# cosmicpifpgaOHL.net
KiCad netlist of a schematic drawn in EAGLE
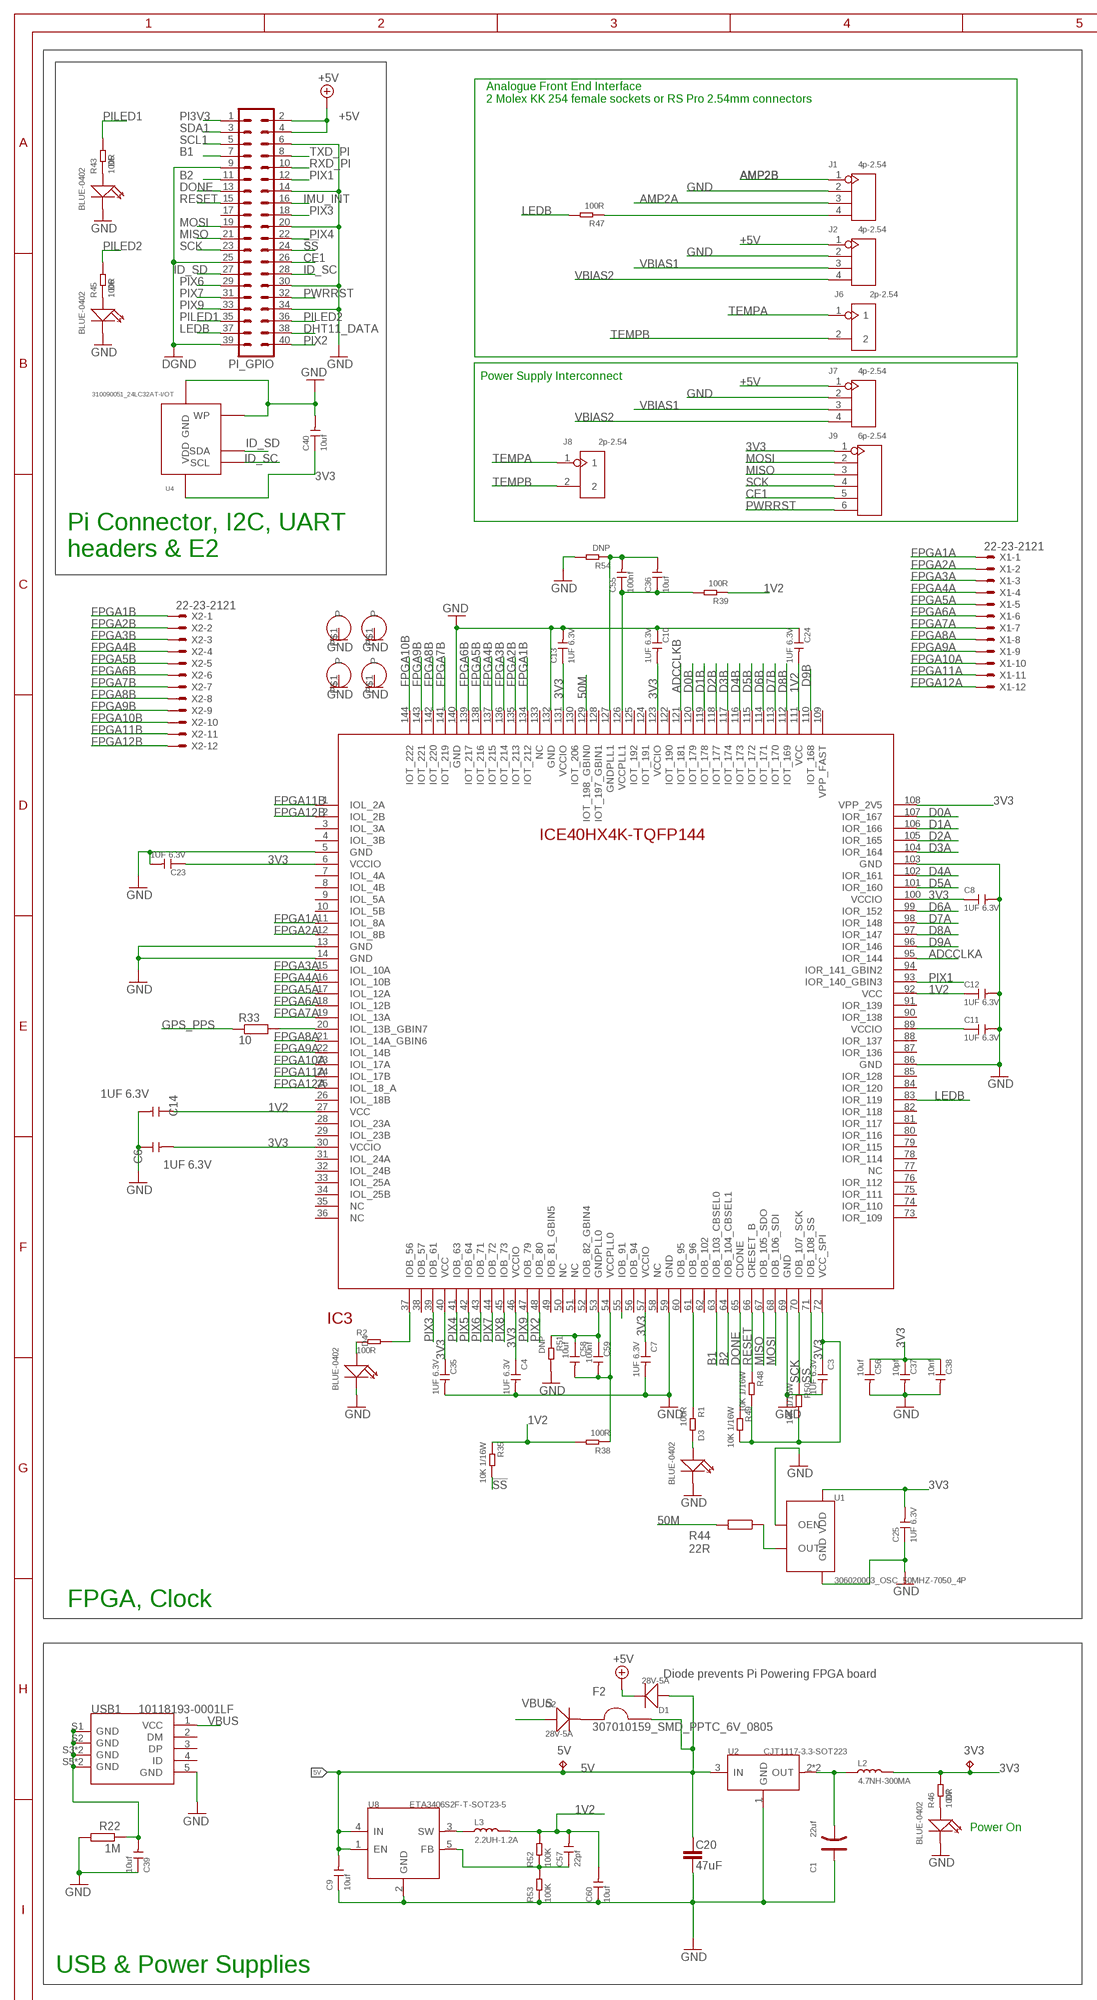
[diagram p0: schematic, sheet 1, part 1 of 2]
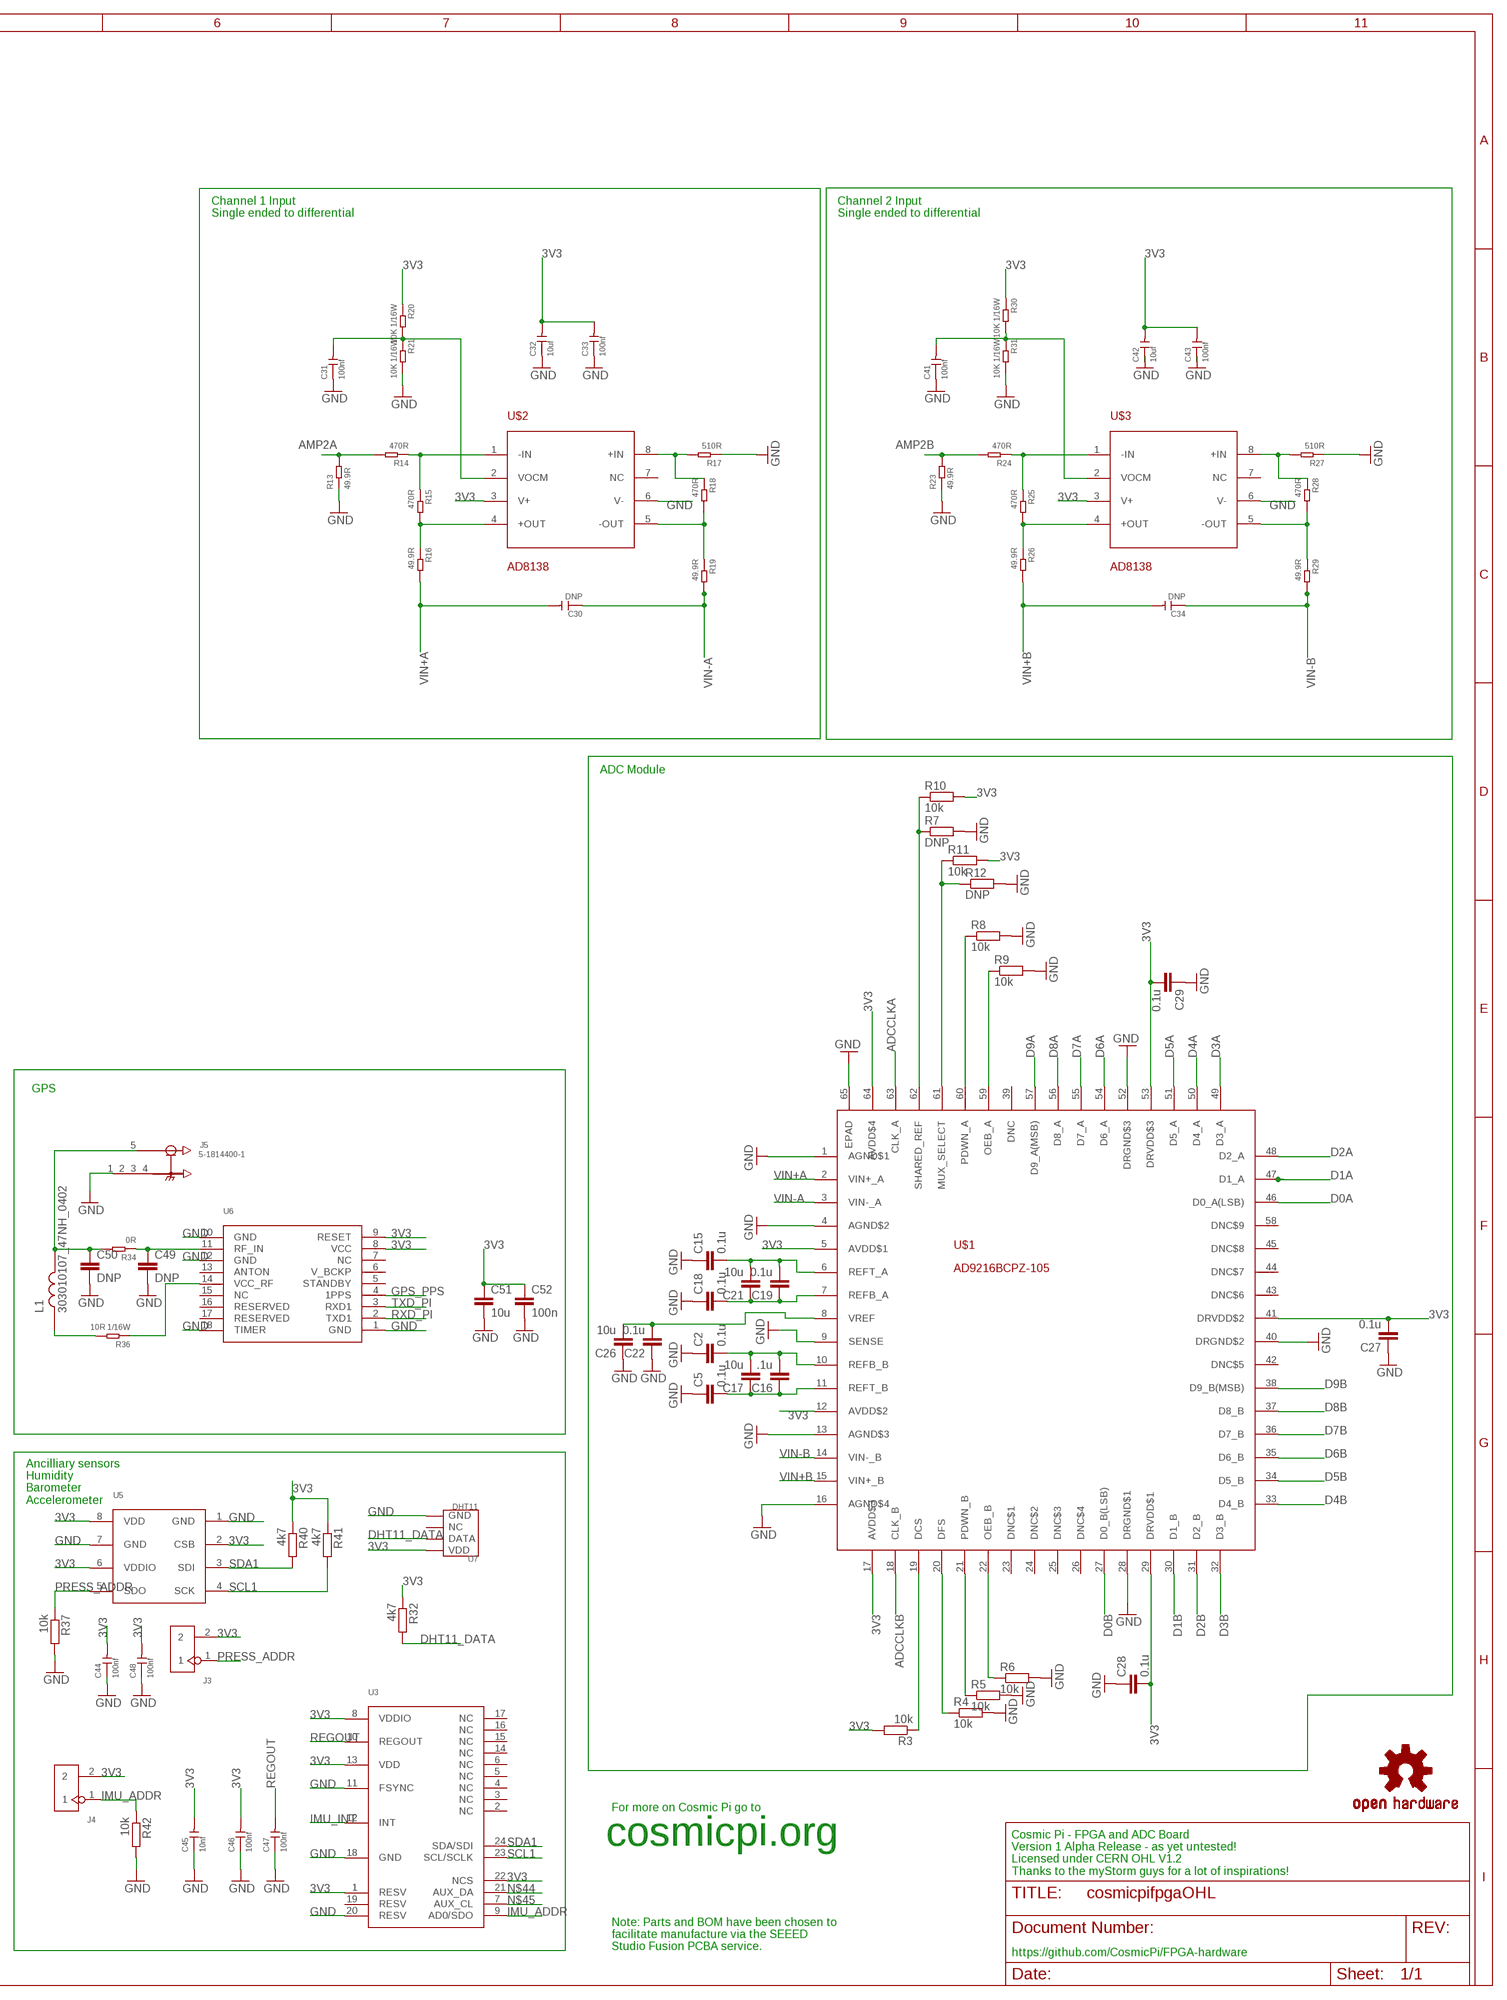
[diagram p1: schematic, sheet 1, part 2 of 2]

(export (version "E")
  (design (tool "Eeschema 10.0.6"))
  (components
    (comp (ref "3V3")
      (value "TPB1,27")
      (footprint "eagle-import:B1,27")
      (libsource (lib "eagle-import") (part "TPB1,27"))
    )
    (comp (ref "5V")
      (value "TPB1,27")
      (footprint "eagle-import:B1,27")
      (libsource (lib "eagle-import") (part "TPB1,27"))
    )
    (comp (ref "C1")
      (value "22uf")
      (footprint "eagle-import:AVX-B")
      (fields (field (name "MPN") "TAJB226K010RNJ"))
      (libsource (lib "eagle-import") (part "TANTALUM-SMD-22UF-10V-10%(AVX-B)"))
    )
    (comp (ref "C2")
      (value "0.1u")
      (footprint "eagle-import:C0402")
      (libsource (lib "eagle-import") (part "C-EUC0402"))
    )
    (comp (ref "C3")
      (value "1UF 6.3V")
      (footprint "eagle-import:C0402")
      (fields (field (name "MPN") "CC0402KRX5R5BB105"))
      (libsource (lib "eagle-import") (part "CERAMIC-1UF-6.3V-10%-X5R(0402)"))
    )
    (comp (ref "C4")
      (value "1UF 6.3V")
      (footprint "eagle-import:C0402")
      (fields (field (name "MPN") "CC0402KRX5R5BB105"))
      (libsource (lib "eagle-import") (part "CERAMIC-1UF-6.3V-10%-X5R(0402)"))
    )
    (comp (ref "C5")
      (value "0.1u")
      (footprint "eagle-import:C0402")
      (libsource (lib "eagle-import") (part "C-EUC0402"))
    )
    (comp (ref "C6")
      (value "1UF 6.3V")
      (footprint "eagle-import:C0402")
      (fields (field (name "MPN") "CC0402KRX5R5BB105"))
      (libsource (lib "eagle-import") (part "CERAMIC-1UF-6.3V-10%-X5R(0402)"))
    )
    (comp (ref "C7")
      (value "1UF 6.3V")
      (footprint "eagle-import:C0402")
      (fields (field (name "MPN") "CC0402KRX5R5BB105"))
      (libsource (lib "eagle-import") (part "CERAMIC-1UF-6.3V-10%-X5R(0402)"))
    )
    (comp (ref "C8")
      (value "1UF 6.3V")
      (footprint "eagle-import:C0402")
      (fields (field (name "MPN") "CC0402KRX5R5BB105"))
      (libsource (lib "eagle-import") (part "CERAMIC-1UF-6.3V-10%-X5R(0402)"))
    )
    (comp (ref "C9")
      (value "10uf")
      (footprint "eagle-import:C0402")
      (fields (field (name "MPN") "CC0402MRX5R5BB106"))
      (libsource (lib "eagle-import") (part "CERAMIC-10UF-6.3V-20%-X5R(0402)"))
    )
    (comp (ref "C10")
      (value "1UF 6.3V")
      (footprint "eagle-import:C0402")
      (fields (field (name "MPN") "CC0402KRX5R5BB105"))
      (libsource (lib "eagle-import") (part "CERAMIC-1UF-6.3V-10%-X5R(0402)"))
    )
    (comp (ref "C11")
      (value "1UF 6.3V")
      (footprint "eagle-import:C0402")
      (fields (field (name "MPN") "CC0402KRX5R5BB105"))
      (libsource (lib "eagle-import") (part "CERAMIC-1UF-6.3V-10%-X5R(0402)"))
    )
    (comp (ref "C12")
      (value "1UF 6.3V")
      (footprint "eagle-import:C0402")
      (fields (field (name "MPN") "CC0402KRX5R5BB105"))
      (libsource (lib "eagle-import") (part "CERAMIC-1UF-6.3V-10%-X5R(0402)"))
    )
    (comp (ref "C13")
      (value "1UF 6.3V")
      (footprint "eagle-import:C0402")
      (fields (field (name "MPN") "CC0402KRX5R5BB105"))
      (libsource (lib "eagle-import") (part "CERAMIC-1UF-6.3V-10%-X5R(0402)"))
    )
    (comp (ref "C14")
      (value "1UF 6.3V")
      (footprint "eagle-import:C0402")
      (fields (field (name "MPN") "CC0402KRX5R5BB105"))
      (libsource (lib "eagle-import") (part "CERAMIC-1UF-6.3V-10%-X5R(0402)"))
    )
    (comp (ref "C15")
      (value "0.1u")
      (footprint "eagle-import:C0402")
      (libsource (lib "eagle-import") (part "C-EUC0402"))
    )
    (comp (ref "C16")
      (value ".1u")
      (footprint "eagle-import:C0402")
      (libsource (lib "eagle-import") (part "C-EUC0402"))
    )
    (comp (ref "C17")
      (value "10u")
      (footprint "eagle-import:C0402")
      (libsource (lib "eagle-import") (part "C-EUC0402"))
    )
    (comp (ref "C18")
      (value "0.1u")
      (footprint "eagle-import:C0402")
      (libsource (lib "eagle-import") (part "C-EUC0402"))
    )
    (comp (ref "C19")
      (value "0.1u")
      (footprint "eagle-import:C0402")
      (libsource (lib "eagle-import") (part "C-EUC0402"))
    )
    (comp (ref "C20")
      (value "47uF")
      (footprint "eagle-import:1206")
      (libsource (lib "eagle-import") (part "C_1206"))
    )
    (comp (ref "C21")
      (value "10u")
      (footprint "eagle-import:C0402")
      (libsource (lib "eagle-import") (part "C-EUC0402"))
    )
    (comp (ref "C22")
      (value "0.1u")
      (footprint "eagle-import:C0402")
      (libsource (lib "eagle-import") (part "C-EUC0402"))
    )
    (comp (ref "C23")
      (value "1UF 6.3V")
      (footprint "eagle-import:C0402")
      (fields (field (name "MPN") "CC0402KRX5R5BB105"))
      (libsource (lib "eagle-import") (part "CERAMIC-1UF-6.3V-10%-X5R(0402)"))
    )
    (comp (ref "C24")
      (value "1UF 6.3V")
      (footprint "eagle-import:C0402")
      (fields (field (name "MPN") "CC0402KRX5R5BB105"))
      (libsource (lib "eagle-import") (part "CERAMIC-1UF-6.3V-10%-X5R(0402)"))
    )
    (comp (ref "C25")
      (value "1UF 6.3V")
      (footprint "eagle-import:C0402")
      (fields (field (name "MPN") "CC0402KRX5R5BB105"))
      (libsource (lib "eagle-import") (part "CERAMIC-1UF-6.3V-10%-X5R(0402)"))
    )
    (comp (ref "C26")
      (value "10u")
      (footprint "eagle-import:C0402")
      (libsource (lib "eagle-import") (part "C-EUC0402"))
    )
    (comp (ref "C27")
      (value "0.1u")
      (footprint "eagle-import:C0402")
      (libsource (lib "eagle-import") (part "C-EUC0402"))
    )
    (comp (ref "C28")
      (value "0.1u")
      (footprint "eagle-import:C0402")
      (libsource (lib "eagle-import") (part "C-EUC0402"))
    )
    (comp (ref "C29")
      (value "0.1u")
      (footprint "eagle-import:C0402")
      (libsource (lib "eagle-import") (part "C-EUC0402"))
    )
    (comp (ref "C30")
      (value "DNP")
      (footprint "eagle-import:C0603")
      (fields (field (name "MPN") "CC0603KRX7R9BB104"))
      (libsource (lib "eagle-import") (part "CERAMIC-100NF-50V-10%-X7R(0603)"))
    )
    (comp (ref "C31")
      (value "100nf")
      (footprint "eagle-import:C0402")
      (fields (field (name "MPN") "CC0402KRX7R8BB104"))
      (libsource (lib "eagle-import") (part "CERAMIC-100NF-25V-10%-X7R(0402)"))
    )
    (comp (ref "C32")
      (value "10uf")
      (footprint "eagle-import:C0402")
      (fields (field (name "MPN") "CC0402MRX5R5BB106"))
      (libsource (lib "eagle-import") (part "CERAMIC-10UF-6.3V-20%-X5R(0402)"))
    )
    (comp (ref "C33")
      (value "100nf")
      (footprint "eagle-import:C0402")
      (fields (field (name "MPN") "CC0402KRX7R8BB104"))
      (libsource (lib "eagle-import") (part "CERAMIC-100NF-25V-10%-X7R(0402)"))
    )
    (comp (ref "C34")
      (value "DNP")
      (footprint "eagle-import:C0603")
      (fields (field (name "MPN") "CC0603KRX7R9BB104"))
      (libsource (lib "eagle-import") (part "CERAMIC-100NF-50V-10%-X7R(0603)"))
    )
    (comp (ref "C35")
      (value "1UF 6.3V")
      (footprint "eagle-import:C0402")
      (fields (field (name "MPN") "CC0402KRX5R5BB105"))
      (libsource (lib "eagle-import") (part "CERAMIC-1UF-6.3V-10%-X5R(0402)"))
    )
    (comp (ref "C36")
      (value "10uf")
      (footprint "eagle-import:C0402")
      (fields (field (name "MPN") "CC0402MRX5R5BB106"))
      (libsource (lib "eagle-import") (part "CERAMIC-10UF-6.3V-20%-X5R(0402)"))
    )
    (comp (ref "C37")
      (value "10pf")
      (footprint "eagle-import:C0402")
      (fields (field (name "MPN") "CC0402JRNPO9BN100"))
      (libsource (lib "eagle-import") (part "CERAMIC-10PF-50V-5%-NPO(0402)"))
    )
    (comp (ref "C38")
      (value "10nf")
      (footprint "eagle-import:C0402")
      (fields (field (name "MPN") "CC0402KRX7R9BB103"))
      (libsource (lib "eagle-import") (part "CERAMIC-10NF-50V-10%-X7R(0402)"))
    )
    (comp (ref "C39")
      (value "10uf")
      (footprint "eagle-import:C0402")
      (fields (field (name "MPN") "CC0402MRX5R5BB106"))
      (libsource (lib "eagle-import") (part "CERAMIC-10UF-6.3V-20%-X5R(0402)"))
    )
    (comp (ref "C40")
      (value "10uf")
      (footprint "eagle-import:C0402")
      (fields (field (name "MPN") "CC0402MRX5R5BB106"))
      (libsource (lib "eagle-import") (part "Seeed-Capacitor_464_CERAMIC-10UF-6.3V-20%-X5R(0402)"))
    )
    (comp (ref "C41")
      (value "100nf")
      (footprint "eagle-import:C0402")
      (fields (field (name "MPN") "CC0402KRX7R8BB104"))
      (libsource (lib "eagle-import") (part "CERAMIC-100NF-25V-10%-X7R(0402)"))
    )
    (comp (ref "C42")
      (value "10uf")
      (footprint "eagle-import:C0402")
      (fields (field (name "MPN") "CC0402MRX5R5BB106"))
      (libsource (lib "eagle-import") (part "CERAMIC-10UF-6.3V-20%-X5R(0402)"))
    )
    (comp (ref "C43")
      (value "100nf")
      (footprint "eagle-import:C0402")
      (fields (field (name "MPN") "CC0402KRX7R8BB104"))
      (libsource (lib "eagle-import") (part "CERAMIC-100NF-25V-10%-X7R(0402)"))
    )
    (comp (ref "C44")
      (value "100nf")
      (footprint "eagle-import:C0402")
      (fields (field (name "MPN") "CC0402KRX7R8BB104"))
      (libsource (lib "eagle-import") (part "Seeed-Capacitor_464_CERAMIC-100NF-25V-10%-X7R(0402)"))
    )
    (comp (ref "C45")
      (value "10nf")
      (footprint "eagle-import:C0402")
      (fields (field (name "MPN") "CC0402KRX7R9BB103"))
      (libsource (lib "eagle-import") (part "Seeed-Capacitor_464_CERAMIC-10NF-50V-10%-X7R(0402)"))
    )
    (comp (ref "C46")
      (value "100nf")
      (footprint "eagle-import:C0402")
      (fields (field (name "MPN") "CC0402KRX7R8BB104"))
      (libsource (lib "eagle-import") (part "Seeed-Capacitor_464_CERAMIC-100NF-25V-10%-X7R(0402)"))
    )
    (comp (ref "C47")
      (value "100nf")
      (footprint "eagle-import:C0402")
      (fields (field (name "MPN") "CC0402KRX7R8BB104"))
      (libsource (lib "eagle-import") (part "Seeed-Capacitor_464_CERAMIC-100NF-25V-10%-X7R(0402)"))
    )
    (comp (ref "C48")
      (value "100nf")
      (footprint "eagle-import:C0402")
      (fields (field (name "MPN") "CC0402KRX7R8BB104"))
      (libsource (lib "eagle-import") (part "Seeed-Capacitor_464_CERAMIC-100NF-25V-10%-X7R(0402)"))
    )
    (comp (ref "C49")
      (value "DNP")
      (footprint "eagle-import:C0402")
      (libsource (lib "eagle-import") (part "C-EUC0402"))
    )
    (comp (ref "C50")
      (value "DNP")
      (footprint "eagle-import:C0402")
      (libsource (lib "eagle-import") (part "C-EUC0402"))
    )
    (comp (ref "C51")
      (value "10u")
      (footprint "eagle-import:C0402")
      (libsource (lib "eagle-import") (part "C-EUC0402"))
    )
    (comp (ref "C52")
      (value "100n")
      (footprint "eagle-import:C0402")
      (libsource (lib "eagle-import") (part "C-EUC0402"))
    )
    (comp (ref "C55")
      (value "100nf")
      (footprint "eagle-import:C0402")
      (fields (field (name "MPN") "CC0402KRX7R8BB104"))
      (libsource (lib "eagle-import") (part "Seeed-Capacitor_464_CERAMIC-100NF-25V-10%-X7R(0402)"))
    )
    (comp (ref "C56")
      (value "10uf")
      (footprint "eagle-import:C0402")
      (fields (field (name "MPN") "CC0402MRX5R5BB106"))
      (libsource (lib "eagle-import") (part "CERAMIC-10UF-6.3V-20%-X5R(0402)"))
    )
    (comp (ref "C57")
      (value "22pf")
      (footprint "eagle-import:C0402")
      (fields (field (name "MPN") "CC0402JRNPO9BN220"))
      (libsource (lib "eagle-import") (part "CERAMIC-22PF-50V-5%-NPO(0402)"))
    )
    (comp (ref "C58")
      (value "10uf")
      (footprint "eagle-import:C0402")
      (fields (field (name "MPN") "CC0402MRX5R5BB106"))
      (libsource (lib "eagle-import") (part "CERAMIC-10UF-6.3V-20%-X5R(0402)"))
    )
    (comp (ref "C59")
      (value "100nf")
      (footprint "eagle-import:C0402")
      (fields (field (name "MPN") "CC0402KRX7R8BB104"))
      (libsource (lib "eagle-import") (part "CERAMIC-100NF-25V-10%-X7R(0402)"))
    )
    (comp (ref "C60")
      (value "10uf")
      (footprint "eagle-import:C0402")
      (fields (field (name "MPN") "CC0402MRX5R5BB106"))
      (libsource (lib "eagle-import") (part "CERAMIC-10UF-6.3V-20%-X5R(0402)"))
    )
    (comp (ref "D1")
      (value "28V-5A")
      (footprint "eagle-import:DO-214AA")
      (fields (field (name "MPN") "SS54B"))
      (libsource (lib "eagle-import") (part "SMD-DIODE-SCHOTTKY-28V-5A(DO-214AA)"))
    )
    (comp (ref "D2")
      (value "28V-5A")
      (footprint "eagle-import:DO-214AA")
      (fields (field (name "MPN") "SS54B"))
      (libsource (lib "eagle-import") (part "SMD-DIODE-SCHOTTKY-28V-5A(DO-214AA)"))
    )
    (comp (ref "D3")
      (value "BLUE-0402")
      (footprint "eagle-import:LED-0402")
      (fields (field (name "MPN") "BL-HB337A-AV-TRB"))
      (libsource (lib "eagle-import") (part "SMD-LED-CLEAR-BLUE(0402)"))
    )
    (comp (ref "D4")
      (value "BLUE-0402")
      (footprint "eagle-import:LED-0402")
      (fields (field (name "MPN") "BL-HB337A-AV-TRB"))
      (libsource (lib "eagle-import") (part "SMD-LED-CLEAR-BLUE(0402)"))
    )
    (comp (ref "D5")
      (value "BLUE-0402")
      (footprint "eagle-import:LED-0402")
      (fields (field (name "MPN") "BL-HB337A-AV-TRB"))
      (libsource (lib "eagle-import") (part "SMD-LED-CLEAR-BLUE(0402)"))
    )
    (comp (ref "D6")
      (value "BLUE-0402")
      (footprint "eagle-import:LED-0402")
      (fields (field (name "MPN") "BL-HB337A-AV-TRB"))
      (libsource (lib "eagle-import") (part "SMD-LED-CLEAR-BLUE(0402)"))
    )
    (comp (ref "D7")
      (value "BLUE-0402")
      (footprint "eagle-import:LED-0402")
      (fields (field (name "MPN") "BL-HB337A-AV-TRB"))
      (libsource (lib "eagle-import") (part "SMD-LED-CLEAR-BLUE(0402)"))
    )
    (comp (ref "F2")
      (value "307010159_SMD_PPTC_6V_0805")
      (footprint "eagle-import:F0805")
      (libsource (lib "eagle-import") (part "307010159_SMD_PPTC_6V_0805"))
    )
    (comp (ref "IC3")
      (value "ICE40HX4K_TQFP144")
      (footprint "eagle-import:TQFP144")
      (libsource (lib "eagle-import") (part "ICE40HX4K_TQFP144"))
    )
    (comp (ref "J1")
      (value "4p-2.54")
      (footprint "eagle-import:H4-2.54")
      (fields (field (name "MPN") "F185-1104A1BSYA1"))
      (libsource (lib "eagle-import") (part "DIP-BLACK-FEMALE-HEADER-VERT(4P-2.54)"))
    )
    (comp (ref "J2")
      (value "4p-2.54")
      (footprint "eagle-import:H4-2.54")
      (fields (field (name "MPN") "F185-1104A1BSYA1"))
      (libsource (lib "eagle-import") (part "DIP-BLACK-FEMALE-HEADER-VERT(4P-2.54)"))
    )
    (comp (ref "J3")
      (value "DIP-BLACK-JUMPER")
      (footprint "eagle-import:H2-2.54")
      (libsource (lib "eagle-import") (part "DIP-BLACK-JUMPER"))
    )
    (comp (ref "J4")
      (value "DIP-BLACK-JUMPER")
      (footprint "eagle-import:H2-2.54")
      (libsource (lib "eagle-import") (part "DIP-BLACK-JUMPER"))
    )
    (comp (ref "J5")
      (value "5-1814400-1")
      (footprint "eagle-import:TE_5-1814400-1")
      (libsource (lib "eagle-import") (part "5-1814400-1"))
    )
    (comp (ref "J6")
      (value "2p-2.54")
      (footprint "eagle-import:H2-2.54")
      (fields (field (name "MPN") "P125-1102A0BS116A1"))
      (libsource (lib "eagle-import") (part "DIP-BLACK-MALE-HEADER-VERT(2P-2.54)"))
    )
    (comp (ref "J7")
      (value "4p-2.54")
      (footprint "eagle-import:H4-2.54")
      (fields (field (name "MPN") "F185-1104A1BSYA1"))
      (libsource (lib "eagle-import") (part "DIP-BLACK-FEMALE-HEADER-VERT(4P-2.54)"))
    )
    (comp (ref "J8")
      (value "2p-2.54")
      (footprint "eagle-import:H2-2.54")
      (fields (field (name "MPN") "P125-1102A0BS116A1"))
      (libsource (lib "eagle-import") (part "DIP-BLACK-MALE-HEADER-VERT(2P-2.54)"))
    )
    (comp (ref "J9")
      (value "6p-2.54")
      (footprint "eagle-import:H6-2.54")
      (fields (field (name "MPN") "F185-1106A1BSYA2"))
      (libsource (lib "eagle-import") (part "DIP-LONG-BLACK-FEMALE-HEADER-VERT(6P-2.54)"))
    )
    (comp (ref "L1")
      (value "303010107_47NH_0402")
      (footprint "eagle-import:L0402")
      (libsource (lib "eagle-import") (part "303010107_47NH_0402"))
    )
    (comp (ref "L2")
      (value "4.7NH-300MA")
      (footprint "eagle-import:L0402")
      (fields (field (name "MPN") "LQG15HS4N7S02"))
      (libsource (lib "eagle-import") (part "SMD-INDUCTOR-4.7NH-0.3NH-300MA(0402)"))
    )
    (comp (ref "L3")
      (value "2.2UH-1.2A")
      (footprint "eagle-import:L0805")
      (fields (field (name "MPN") "LQM2MPN2R2MG0"))
      (libsource (lib "eagle-import") (part "SMD-INDUCTOR-2.2UH-20%-1.2A(0805)"))
    )
    (comp (ref "OSHW")
      (value "OSHW-LOGOL")
      (footprint "eagle-import:OSHW-LOGO-L")
      (libsource (lib "eagle-import") (part "OSHW-LOGOL"))
    )
    (comp (ref "PI_GPIO")
      (value "MA20-2")
      (footprint "eagle-import:MA20-2")
      (libsource (lib "eagle-import") (part "MA20-2"))
    )
    (comp (ref "R1")
      (value "100R")
      (footprint "eagle-import:R0402")
      (fields (field (name "MPN") "RC0402JR-07100RL"))
      (libsource (lib "eagle-import") (part "Seeed-Resistor_474_SMD-RES-100R-5%-1/16W(0402)"))
    )
    (comp (ref "R2")
      (value "100R")
      (footprint "eagle-import:R0402")
      (fields (field (name "MPN") "RC0402JR-07100RL"))
      (libsource (lib "eagle-import") (part "Seeed-Resistor_474_SMD-RES-100R-5%-1/16W(0402)"))
    )
    (comp (ref "R3")
      (value "10k")
      (footprint "eagle-import:R0402")
      (libsource (lib "eagle-import") (part "R-EU_R0402"))
    )
    (comp (ref "R4")
      (value "10k")
      (footprint "eagle-import:R0402")
      (libsource (lib "eagle-import") (part "R-EU_R0402"))
    )
    (comp (ref "R5")
      (value "10k")
      (footprint "eagle-import:R0402")
      (libsource (lib "eagle-import") (part "R-EU_R0402"))
    )
    (comp (ref "R6")
      (value "10k")
      (footprint "eagle-import:R0402")
      (libsource (lib "eagle-import") (part "R-EU_R0402"))
    )
    (comp (ref "R7")
      (value "DNP")
      (footprint "eagle-import:R0402")
      (libsource (lib "eagle-import") (part "R-EU_R0402"))
    )
    (comp (ref "R8")
      (value "10k")
      (footprint "eagle-import:R0402")
      (libsource (lib "eagle-import") (part "R-EU_R0402"))
    )
    (comp (ref "R9")
      (value "10k")
      (footprint "eagle-import:R0402")
      (libsource (lib "eagle-import") (part "R-EU_R0402"))
    )
    (comp (ref "R10")
      (value "10k")
      (footprint "eagle-import:R0402")
      (libsource (lib "eagle-import") (part "R-EU_R0402"))
    )
    (comp (ref "R11")
      (value "10k")
      (footprint "eagle-import:R0402")
      (libsource (lib "eagle-import") (part "R-EU_R0402"))
    )
    (comp (ref "R12")
      (value "DNP")
      (footprint "eagle-import:R0402")
      (libsource (lib "eagle-import") (part "R-EU_R0402"))
    )
    (comp (ref "R13")
      (value "49.9R")
      (footprint "eagle-import:R0603")
      (fields (field (name "MPN") "RC0603FR-0749R9L"))
      (libsource (lib "eagle-import") (part "SMD-RES-49.9R-1%-1/10W(0603)"))
    )
    (comp (ref "R14")
      (value "470R")
      (footprint "eagle-import:R0603")
      (fields (field (name "MPN") "RC0603JR-07470RL"))
      (libsource (lib "eagle-import") (part "SMD-RES-470R-5%-1/10W(0603)"))
    )
    (comp (ref "R15")
      (value "470R")
      (footprint "eagle-import:R0603")
      (fields (field (name "MPN") "RC0603JR-07470RL"))
      (libsource (lib "eagle-import") (part "SMD-RES-470R-5%-1/10W(0603)"))
    )
    (comp (ref "R16")
      (value "49.9R")
      (footprint "eagle-import:R0603")
      (fields (field (name "MPN") "RC0603FR-0749R9L"))
      (libsource (lib "eagle-import") (part "SMD-RES-49.9R-1%-1/10W(0603)"))
    )
    (comp (ref "R17")
      (value "510R")
      (footprint "eagle-import:R0603")
      (fields (field (name "MPN") "RC0603JR-07510RL"))
      (libsource (lib "eagle-import") (part "SMD-RES-510R-5%-1/10W(0603)"))
    )
    (comp (ref "R18")
      (value "470R")
      (footprint "eagle-import:R0603")
      (fields (field (name "MPN") "RC0603JR-07470RL"))
      (libsource (lib "eagle-import") (part "SMD-RES-470R-5%-1/10W(0603)"))
    )
    (comp (ref "R19")
      (value "49.9R")
      (footprint "eagle-import:R0603")
      (fields (field (name "MPN") "RC0603FR-0749R9L"))
      (libsource (lib "eagle-import") (part "SMD-RES-49.9R-1%-1/10W(0603)"))
    )
    (comp (ref "R20")
      (value "10K 1/16W")
      (footprint "eagle-import:R0402")
      (fields (field (name "MPN") "RC0402FR-0710KL"))
      (libsource (lib "eagle-import") (part "SMD-RES-10K-1%-1/16W(0402)"))
    )
    (comp (ref "R21")
      (value "10K 1/16W")
      (footprint "eagle-import:R0402")
      (fields (field (name "MPN") "RC0402FR-0710KL"))
      (libsource (lib "eagle-import") (part "SMD-RES-10K-1%-1/16W(0402)"))
    )
    (comp (ref "R22")
      (value "1M")
      (footprint "eagle-import:R0402")
      (libsource (lib "eagle-import") (part "R-EU_R0402"))
    )
    (comp (ref "R23")
      (value "49.9R")
      (footprint "eagle-import:R0603")
      (fields (field (name "MPN") "RC0603FR-0749R9L"))
      (libsource (lib "eagle-import") (part "SMD-RES-49.9R-1%-1/10W(0603)"))
    )
    (comp (ref "R24")
      (value "470R")
      (footprint "eagle-import:R0603")
      (fields (field (name "MPN") "RC0603JR-07470RL"))
      (libsource (lib "eagle-import") (part "SMD-RES-470R-5%-1/10W(0603)"))
    )
    (comp (ref "R25")
      (value "470R")
      (footprint "eagle-import:R0603")
      (fields (field (name "MPN") "RC0603JR-07470RL"))
      (libsource (lib "eagle-import") (part "SMD-RES-470R-5%-1/10W(0603)"))
    )
    (comp (ref "R26")
      (value "49.9R")
      (footprint "eagle-import:R0603")
      (fields (field (name "MPN") "RC0603FR-0749R9L"))
      (libsource (lib "eagle-import") (part "SMD-RES-49.9R-1%-1/10W(0603)"))
    )
    (comp (ref "R27")
      (value "510R")
      (footprint "eagle-import:R0603")
      (fields (field (name "MPN") "RC0603JR-07510RL"))
      (libsource (lib "eagle-import") (part "SMD-RES-510R-5%-1/10W(0603)"))
    )
    (comp (ref "R28")
      (value "470R")
      (footprint "eagle-import:R0603")
      (fields (field (name "MPN") "RC0603JR-07470RL"))
      (libsource (lib "eagle-import") (part "SMD-RES-470R-5%-1/10W(0603)"))
    )
    (comp (ref "R29")
      (value "49.9R")
      (footprint "eagle-import:R0603")
      (fields (field (name "MPN") "RC0603FR-0749R9L"))
      (libsource (lib "eagle-import") (part "SMD-RES-49.9R-1%-1/10W(0603)"))
    )
    (comp (ref "R30")
      (value "10K 1/16W")
      (footprint "eagle-import:R0402")
      (fields (field (name "MPN") "RC0402FR-0710KL"))
      (libsource (lib "eagle-import") (part "SMD-RES-10K-1%-1/16W(0402)"))
    )
    (comp (ref "R31")
      (value "10K 1/16W")
      (footprint "eagle-import:R0402")
      (fields (field (name "MPN") "RC0402FR-0710KL"))
      (libsource (lib "eagle-import") (part "SMD-RES-10K-1%-1/16W(0402)"))
    )
    (comp (ref "R32")
      (value "4k7")
      (footprint "eagle-import:R0402")
      (libsource (lib "eagle-import") (part "R-EU_R0402"))
    )
    (comp (ref "R33")
      (value "10")
      (footprint "eagle-import:R0402")
      (libsource (lib "eagle-import") (part "R-EU_R0402"))
    )
    (comp (ref "R34")
      (value "0R")
      (footprint "eagle-import:R0402")
      (fields (field (name "MPN") "RC0402JR-070RL"))
      (libsource (lib "eagle-import") (part "SMD-RES-0R-5%-1/16W(0402)"))
    )
    (comp (ref "R35")
      (value "10K 1/16W")
      (footprint "eagle-import:R0402")
      (fields (field (name "MPN") "RC0402FR-0710KL"))
      (libsource (lib "eagle-import") (part "SMD-RES-10K-1%-1/16W(0402)"))
    )
    (comp (ref "R36")
      (value "10R 1/16W")
      (footprint "eagle-import:R0402")
      (fields (field (name "MPN") "RC0402FR-0710RL"))
      (libsource (lib "eagle-import") (part "SMD-RES-10R-1%-1/16W(0402)"))
    )
    (comp (ref "R37")
      (value "10k")
      (footprint "eagle-import:R0402")
      (libsource (lib "eagle-import") (part "R-EU_R0402"))
    )
    (comp (ref "R38")
      (value "100R")
      (footprint "eagle-import:R0402")
      (fields (field (name "MPN") "RC0402JR-07100RL"))
      (libsource (lib "eagle-import") (part "SMD-RES-100R-5%-1/16W(0402)"))
    )
    (comp (ref "R39")
      (value "100R")
      (footprint "eagle-import:R0402")
      (fields (field (name "MPN") "RC0402JR-07100RL"))
      (libsource (lib "eagle-import") (part "SMD-RES-100R-5%-1/16W(0402)"))
    )
    (comp (ref "R40")
      (value "4k7")
      (footprint "eagle-import:R0402")
      (libsource (lib "eagle-import") (part "R-EU_R0402"))
    )
    (comp (ref "R41")
      (value "4k7")
      (footprint "eagle-import:R0402")
      (libsource (lib "eagle-import") (part "R-EU_R0402"))
    )
    (comp (ref "R42")
      (value "10k")
      (footprint "eagle-import:R0402")
      (libsource (lib "eagle-import") (part "R-EU_R0402"))
    )
    (comp (ref "R43")
      (value "100R")
      (footprint "eagle-import:R0402")
      (fields (field (name "MPN") "RC0402JR-07100RL"))
      (libsource (lib "eagle-import") (part "Seeed-Resistor_474_SMD-RES-100R-5%-1/16W(0402)"))
    )
    (comp (ref "R44")
      (value "22R")
      (footprint "eagle-import:R0402")
      (libsource (lib "eagle-import") (part "R-EU_R0402"))
    )
    (comp (ref "R45")
      (value "100R")
      (footprint "eagle-import:R0402")
      (fields (field (name "MPN") "RC0402JR-07100RL"))
      (libsource (lib "eagle-import") (part "Seeed-Resistor_474_SMD-RES-100R-5%-1/16W(0402)"))
    )
    (comp (ref "R46")
      (value "100R")
      (footprint "eagle-import:R0402")
      (fields (field (name "MPN") "RC0402JR-07100RL"))
      (libsource (lib "eagle-import") (part "Seeed-Resistor_474_SMD-RES-100R-5%-1/16W(0402)"))
    )
    (comp (ref "R47")
      (value "100R")
      (footprint "eagle-import:R0402")
      (fields (field (name "MPN") "RC0402JR-07100RL"))
      (libsource (lib "eagle-import") (part "Seeed-Resistor_474_SMD-RES-100R-5%-1/16W(0402)"))
    )
    (comp (ref "R48")
      (value "10K 1/16W")
      (footprint "eagle-import:R0402")
      (fields (field (name "MPN") "RC0402FR-0710KL"))
      (libsource (lib "eagle-import") (part "SMD-RES-10K-1%-1/16W(0402)"))
    )
    (comp (ref "R49")
      (value "10K 1/16W")
      (footprint "eagle-import:R0402")
      (fields (field (name "MPN") "RC0402FR-0710KL"))
      (libsource (lib "eagle-import") (part "SMD-RES-10K-1%-1/16W(0402)"))
    )
    (comp (ref "R50")
      (value "10K 1/16W")
      (footprint "eagle-import:R0402")
      (fields (field (name "MPN") "RC0402FR-0710KL"))
      (libsource (lib "eagle-import") (part "SMD-RES-10K-1%-1/16W(0402)"))
    )
    (comp (ref "R51")
      (value "DNP")
      (footprint "eagle-import:R0402")
      (fields (field (name "MPN") "RC0402JR-07100RL"))
      (libsource (lib "eagle-import") (part "Seeed-Resistor_474_SMD-RES-100R-5%-1/16W(0402)"))
    )
    (comp (ref "R52")
      (value "100K")
      (footprint "eagle-import:R0402")
      (fields (field (name "MPN") "RC0402FR-07100KL"))
      (libsource (lib "eagle-import") (part "SMD-RES-100K-1%-1/16W(0402)"))
    )
    (comp (ref "R53")
      (value "100K")
      (footprint "eagle-import:R0402")
      (fields (field (name "MPN") "RC0402FR-07100KL"))
      (libsource (lib "eagle-import") (part "SMD-RES-100K-1%-1/16W(0402)"))
    )
    (comp (ref "R54")
      (value "DNP")
      (footprint "eagle-import:R0402")
      (fields (field (name "MPN") "RC0402JR-07100RL"))
      (libsource (lib "eagle-import") (part "SMD-RES-100R-5%-1/16W(0402)"))
    )
    (comp (ref "U$1")
      (value "AD9216BCPZ-105")
      (footprint "eagle-import:QFN50P900X900X100-65N")
      (libsource (lib "eagle-import") (part "AD9216BCPZ-105"))
    )
    (comp (ref "U$2")
      (value "AD8138")
      (footprint "eagle-import:SOP65P490X110-8N")
      (libsource (lib "eagle-import") (part "AD8138"))
    )
    (comp (ref "U$3")
      (value "AD8138")
      (footprint "eagle-import:SOP65P490X110-8N")
      (libsource (lib "eagle-import") (part "AD8138"))
    )
    (comp (ref "U$16")
      (value "HOLE-2.5MM")
      (footprint "eagle-import:2.5MM-HOLE")
      (libsource (lib "eagle-import") (part "HOLE-2.5MM"))
    )
    (comp (ref "U$21")
      (value "HOLE-2.5MM")
      (footprint "eagle-import:2.5MM-HOLE")
      (libsource (lib "eagle-import") (part "HOLE-2.5MM"))
    )
    (comp (ref "U$22")
      (value "HOLE-2.5MM")
      (footprint "eagle-import:2.5MM-HOLE")
      (libsource (lib "eagle-import") (part "HOLE-2.5MM"))
    )
    (comp (ref "U$24")
      (value "HOLE-2.5MM")
      (footprint "eagle-import:2.5MM-HOLE")
      (libsource (lib "eagle-import") (part "HOLE-2.5MM"))
    )
    (comp (ref "U1")
      (value "306020003_OSC_50MHZ-7050_4P")
      (footprint "eagle-import:X7050_4P")
      (libsource (lib "eagle-import") (part "306020003_OSC_50MHZ-7050_4P"))
    )
    (comp (ref "U2")
      (value "CJT1117-3.3-SOT223")
      (footprint "eagle-import:SOT-223")
      (fields (field (name "MPN") "CJT1117-3.3"))
      (libsource (lib "eagle-import") (part "PMIC-CJT1117-3.3(SOT223)"))
    )
    (comp (ref "U3")
      (value "MPU-9250")
      (footprint "eagle-import:MPU-9250")
      (libsource (lib "eagle-import") (part "MPU-9250"))
    )
    (comp (ref "U4")
      (value "310090051_24LC32AT-I/OT")
      (footprint "eagle-import:SOT235")
      (libsource (lib "eagle-import") (part "310090051_24LC32AT-I/OT"))
    )
    (comp (ref "U5")
      (value "BMP280")
      (footprint "eagle-import:BMP280")
      (libsource (lib "eagle-import") (part "BMP280"))
    )
    (comp (ref "U6")
      (value "L70-M39")
      (footprint "eagle-import:L70-M39")
      (libsource (lib "eagle-import") (part "L70-M39"))
    )
    (comp (ref "U7")
      (value "DHT11")
      (footprint "eagle-import:SNR4-2.54-15.5X12.0X5.5MM")
      (libsource (lib "eagle-import") (part "TEM-HUM-DHT11(4P-15.5X12.0MM)"))
    )
    (comp (ref "U8")
      (value "ETA3406S2F-T-SOT23-5")
      (footprint "eagle-import:SOT-23-5")
      (fields (field (name "MPN") "ETA3406S2F-T"))
      (libsource (lib "eagle-import") (part "PMIC-DC-DC-ETA3406S2F-T(SOT23-5)"))
    )
    (comp (ref "USB1")
      (value "10118193-0001LF")
      (footprint "eagle-import:MICRO-USB5+6P-SMD-0.65-B")
      (libsource (lib "eagle-import") (part "MICRO-USB-SMD-B-(10118193-0001LF)"))
    )
    (comp (ref "X1")
      (value "22-23-2121")
      (footprint "eagle-import:22-23-2121")
      (fields (field (name "MF") "MOLEX"))
      (libsource (lib "eagle-import") (part "22-23-2121"))
    )
    (comp (ref "X2")
      (value "22-23-2121")
      (footprint "eagle-import:22-23-2121")
      (fields (field (name "MF") "MOLEX"))
      (libsource (lib "eagle-import") (part "22-23-2121"))
    )
  )
  (nets
    (net (code "1") (name "+5V") (class "Default")
      (node (ref "D1") (pin "-") (pinfunction "-_-") (pintype "passive"))
      (node (ref "J2") (pin "1") (pinfunction "P$1_1") (pintype "bidirectional"))
      (node (ref "J7") (pin "1") (pinfunction "P$1_1") (pintype "bidirectional"))
      (node (ref "PI_GPIO") (pin "2") (pinfunction "2_2") (pintype "passive"))
      (node (ref "PI_GPIO") (pin "4") (pinfunction "4_4") (pintype "passive"))
    )
    (net (code "2") (name "/1V2") (class "Default")
      (node (ref "C12") (pin "1") (pinfunction "1_1") (pintype "passive"))
      (node (ref "C14") (pin "1") (pinfunction "1_1") (pintype "passive"))
      (node (ref "C24") (pin "2") (pinfunction "2_2") (pintype "passive"))
      (node (ref "C57") (pin "2") (pinfunction "2_2") (pintype "passive"))
      (node (ref "C60") (pin "2") (pinfunction "2_2") (pintype "passive"))
      (node (ref "IC3") (pin "111") (pinfunction "VCC_111") (pintype "bidirectional"))
      (node (ref "IC3") (pin "27") (pinfunction "VCC_27") (pintype "bidirectional"))
      (node (ref "IC3") (pin "92") (pinfunction "VCC_92") (pintype "bidirectional"))
      (node (ref "L3") (pin "2") (pinfunction "2_2") (pintype "passive"))
      (node (ref "R35") (pin "1") (pinfunction "1_1") (pintype "passive"))
      (node (ref "R38") (pin "2") (pinfunction "2_2") (pintype "passive"))
      (node (ref "R39") (pin "1") (pinfunction "1_1") (pintype "passive"))
      (node (ref "R52") (pin "2") (pinfunction "2_2") (pintype "passive"))
    )
    (net (code "3") (name "/3V3") (class "Default")
      (node (ref "3V3") (pin "TP") (pinfunction "TP_TP") (pintype "input"))
      (node (ref "C10") (pin "2") (pinfunction "2_2") (pintype "passive"))
      (node (ref "C13") (pin "1") (pinfunction "1_1") (pintype "passive"))
      (node (ref "C23") (pin "1") (pinfunction "1_1") (pintype "passive"))
      (node (ref "C25") (pin "2") (pinfunction "2_2") (pintype "passive"))
      (node (ref "C27") (pin "2") (pinfunction "2_2") (pintype "passive"))
      (node (ref "C28") (pin "2") (pinfunction "2_2") (pintype "passive"))
      (node (ref "C29") (pin "2") (pinfunction "2_2") (pintype "passive"))
      (node (ref "C3") (pin "1") (pinfunction "1_1") (pintype "passive"))
      (node (ref "C32") (pin "2") (pinfunction "2_2") (pintype "passive"))
      (node (ref "C33") (pin "2") (pinfunction "2_2") (pintype "passive"))
      (node (ref "C35") (pin "1") (pinfunction "1_1") (pintype "passive"))
      (node (ref "C37") (pin "1") (pinfunction "1_1") (pintype "passive"))
      (node (ref "C38") (pin "1") (pinfunction "1_1") (pintype "passive"))
      (node (ref "C4") (pin "1") (pinfunction "1_1") (pintype "passive"))
      (node (ref "C40") (pin "1") (pinfunction "1_1") (pintype "passive"))
      (node (ref "C42") (pin "2") (pinfunction "2_2") (pintype "passive"))
      (node (ref "C43") (pin "2") (pinfunction "2_2") (pintype "passive"))
      (node (ref "C44") (pin "2") (pinfunction "2_2") (pintype "passive"))
      (node (ref "C45") (pin "2") (pinfunction "2_2") (pintype "passive"))
      (node (ref "C46") (pin "2") (pinfunction "2_2") (pintype "passive"))
      (node (ref "C48") (pin "2") (pinfunction "2_2") (pintype "passive"))
      (node (ref "C51") (pin "1") (pinfunction "1_1") (pintype "passive"))
      (node (ref "C52") (pin "1") (pinfunction "1_1") (pintype "passive"))
      (node (ref "C56") (pin "1") (pinfunction "1_1") (pintype "passive"))
      (node (ref "C6") (pin "2") (pinfunction "2_2") (pintype "passive"))
      (node (ref "C7") (pin "1") (pinfunction "1_1") (pintype "passive"))
      (node (ref "C8") (pin "1") (pinfunction "1_1") (pintype "passive"))
      (node (ref "IC3") (pin "100") (pinfunction "VCCIO_100") (pintype "bidirectional"))
      (node (ref "IC3") (pin "108") (pinfunction "VPP_2V5_108") (pintype "bidirectional"))
      (node (ref "IC3") (pin "123") (pinfunction "VCCIO_123") (pintype "bidirectional"))
      (node (ref "IC3") (pin "131") (pinfunction "VCCIO_131") (pintype "bidirectional"))
      (node (ref "IC3") (pin "30") (pinfunction "VCCIO_30") (pintype "bidirectional"))
      (node (ref "IC3") (pin "40") (pinfunction "VCC_40") (pintype "bidirectional"))
      (node (ref "IC3") (pin "46") (pinfunction "VCCIO_46") (pintype "bidirectional"))
      (node (ref "IC3") (pin "57") (pinfunction "VCCIO_57") (pintype "bidirectional"))
      (node (ref "IC3") (pin "6") (pinfunction "VCCIO_6") (pintype "bidirectional"))
      (node (ref "IC3") (pin "72") (pinfunction "VCC_SPI_72") (pintype "bidirectional"))
      (node (ref "J3") (pin "2") (pinfunction "2_2") (pintype "bidirectional"))
      (node (ref "J4") (pin "2") (pinfunction "2_2") (pintype "bidirectional"))
      (node (ref "J9") (pin "1") (pinfunction "1_1") (pintype "bidirectional"))
      (node (ref "L2") (pin "2") (pinfunction "2_2") (pintype "passive"))
      (node (ref "R10") (pin "2") (pinfunction "2_2") (pintype "passive"))
      (node (ref "R11") (pin "2") (pinfunction "2_2") (pintype "passive"))
      (node (ref "R20") (pin "1") (pinfunction "1_1") (pintype "passive"))
      (node (ref "R3") (pin "2") (pinfunction "2_2") (pintype "passive"))
      (node (ref "R30") (pin "1") (pinfunction "1_1") (pintype "passive"))
      (node (ref "R32") (pin "1") (pinfunction "1_1") (pintype "passive"))
      (node (ref "R40") (pin "1") (pinfunction "1_1") (pintype "passive"))
      (node (ref "R41") (pin "1") (pinfunction "1_1") (pintype "passive"))
      (node (ref "R46") (pin "2") (pinfunction "2_2") (pintype "passive"))
      (node (ref "R48") (pin "2") (pinfunction "2_2") (pintype "passive"))
      (node (ref "R49") (pin "2") (pinfunction "2_2") (pintype "passive"))
      (node (ref "R50") (pin "2") (pinfunction "2_2") (pintype "passive"))
      (node (ref "U$1") (pin "12") (pinfunction "AVDD$2_12") (pintype "bidirectional"))
      (node (ref "U$1") (pin "17") (pinfunction "AVDD$3_17") (pintype "bidirectional"))
      (node (ref "U$1") (pin "29") (pinfunction "DRVDD$1_29") (pintype "bidirectional"))
      (node (ref "U$1") (pin "41") (pinfunction "DRVDD$2_41") (pintype "bidirectional"))
      (node (ref "U$1") (pin "5") (pinfunction "AVDD$1_5") (pintype "bidirectional"))
      (node (ref "U$1") (pin "53") (pinfunction "DRVDD$3_53") (pintype "bidirectional"))
      (node (ref "U$1") (pin "64") (pinfunction "AVDD$4_64") (pintype "bidirectional"))
      (node (ref "U$2") (pin "3") (pinfunction "V+_3") (pintype "bidirectional"))
      (node (ref "U$3") (pin "3") (pinfunction "V+_3") (pintype "bidirectional"))
      (node (ref "U1") (pin "P$4") (pinfunction "VDD_P$4") (pintype "power_in"))
      (node (ref "U3") (pin "1") (pinfunction "RESV_1") (pintype "bidirectional"))
      (node (ref "U3") (pin "13") (pinfunction "VDD_13") (pintype "bidirectional"))
      (node (ref "U3") (pin "22") (pinfunction "NCS_22") (pintype "bidirectional"))
      (node (ref "U3") (pin "8") (pinfunction "VDDIO_8") (pintype "bidirectional"))
      (node (ref "U4") (pin "4") (pinfunction "VDD_4") (pintype "power_in"))
      (node (ref "U5") (pin "2") (pinfunction "CSB_2") (pintype "bidirectional"))
      (node (ref "U5") (pin "6") (pinfunction "VDDIO_6") (pintype "bidirectional"))
      (node (ref "U5") (pin "8") (pinfunction "VDD_8") (pintype "bidirectional"))
      (node (ref "U6") (pin "8") (pinfunction "VCC_8") (pintype "bidirectional"))
      (node (ref "U6") (pin "9") (pinfunction "RESET_9") (pintype "bidirectional"))
      (node (ref "U7") (pin "1") (pinfunction "VDD_1") (pintype "power_in"))
    )
    (net (code "4") (name "/50M") (class "Default")
      (node (ref "IC3") (pin "129") (pinfunction "IOT_198_GBIN0_129") (pintype "bidirectional"))
      (node (ref "R44") (pin "2") (pinfunction "2_2") (pintype "passive"))
    )
    (net (code "5") (name "/ADCCLKA") (class "Default")
      (node (ref "IC3") (pin "95") (pinfunction "IOR_144_95") (pintype "bidirectional"))
      (node (ref "U$1") (pin "63") (pinfunction "CLK_A_63") (pintype "bidirectional"))
    )
    (net (code "6") (name "/ADCCLKB") (class "Default")
      (node (ref "IC3") (pin "121") (pinfunction "IOT_181_121") (pintype "bidirectional"))
      (node (ref "U$1") (pin "18") (pinfunction "CLK_B_18") (pintype "bidirectional"))
    )
    (net (code "7") (name "/AMP2A") (class "Default")
      (node (ref "J1") (pin "3") (pinfunction "P$3_3") (pintype "bidirectional"))
      (node (ref "R13") (pin "2") (pinfunction "2_2") (pintype "passive"))
      (node (ref "R14") (pin "2") (pinfunction "2_2") (pintype "passive"))
    )
    (net (code "8") (name "/AMP2B") (class "Default")
      (node (ref "J1") (pin "1") (pinfunction "P$1_1") (pintype "bidirectional"))
      (node (ref "R23") (pin "2") (pinfunction "2_2") (pintype "passive"))
      (node (ref "R24") (pin "2") (pinfunction "2_2") (pintype "passive"))
    )
    (net (code "9") (name "/B1") (class "Default")
      (node (ref "IC3") (pin "63") (pinfunction "IOB_103_CBSEL0_63") (pintype "bidirectional"))
      (node (ref "PI_GPIO") (pin "7") (pinfunction "7_7") (pintype "passive"))
    )
    (net (code "10") (name "/B2") (class "Default")
      (node (ref "IC3") (pin "64") (pinfunction "IOB_104_CBSEL1_64") (pintype "bidirectional"))
      (node (ref "PI_GPIO") (pin "11") (pinfunction "11_11") (pintype "passive"))
    )
    (net (code "11") (name "/CE1") (class "Default")
      (node (ref "J9") (pin "5") (pinfunction "5_5") (pintype "bidirectional"))
      (node (ref "PI_GPIO") (pin "26") (pinfunction "26_26") (pintype "passive"))
    )
    (net (code "12") (name "/D0A") (class "Default")
      (node (ref "IC3") (pin "107") (pinfunction "IOR_167_107") (pintype "bidirectional"))
      (node (ref "U$1") (pin "46") (pinfunction "D0_A(LSB)_46") (pintype "bidirectional"))
    )
    (net (code "13") (name "/D0B") (class "Default")
      (node (ref "IC3") (pin "120") (pinfunction "IOT_179_120") (pintype "bidirectional"))
      (node (ref "U$1") (pin "27") (pinfunction "D0_B(LSB)_27") (pintype "bidirectional"))
    )
    (net (code "14") (name "/D1A") (class "Default")
      (node (ref "IC3") (pin "106") (pinfunction "IOR_166_106") (pintype "bidirectional"))
      (node (ref "U$1") (pin "47") (pinfunction "D1_A_47") (pintype "bidirectional"))
    )
    (net (code "15") (name "/D1B") (class "Default")
      (node (ref "IC3") (pin "119") (pinfunction "IOT_178_119") (pintype "bidirectional"))
      (node (ref "U$1") (pin "30") (pinfunction "D1_B_30") (pintype "bidirectional"))
    )
    (net (code "16") (name "/D2A") (class "Default")
      (node (ref "IC3") (pin "105") (pinfunction "IOR_165_105") (pintype "bidirectional"))
      (node (ref "U$1") (pin "48") (pinfunction "D2_A_48") (pintype "bidirectional"))
    )
    (net (code "17") (name "/D2B") (class "Default")
      (node (ref "IC3") (pin "118") (pinfunction "IOT_177_118") (pintype "bidirectional"))
      (node (ref "U$1") (pin "31") (pinfunction "D2_B_31") (pintype "bidirectional"))
    )
    (net (code "18") (name "/D3A") (class "Default")
      (node (ref "IC3") (pin "104") (pinfunction "IOR_164_104") (pintype "bidirectional"))
      (node (ref "U$1") (pin "49") (pinfunction "D3_A_49") (pintype "bidirectional"))
    )
    (net (code "19") (name "/D3B") (class "Default")
      (node (ref "IC3") (pin "117") (pinfunction "IOT_174_117") (pintype "bidirectional"))
      (node (ref "U$1") (pin "32") (pinfunction "D3_B_32") (pintype "bidirectional"))
    )
    (net (code "20") (name "/D4A") (class "Default")
      (node (ref "IC3") (pin "102") (pinfunction "IOR_161_102") (pintype "bidirectional"))
      (node (ref "U$1") (pin "50") (pinfunction "D4_A_50") (pintype "bidirectional"))
    )
    (net (code "21") (name "/D4B") (class "Default")
      (node (ref "IC3") (pin "116") (pinfunction "IOT_173_116") (pintype "bidirectional"))
      (node (ref "U$1") (pin "33") (pinfunction "D4_B_33") (pintype "bidirectional"))
    )
    (net (code "22") (name "/D5A") (class "Default")
      (node (ref "IC3") (pin "101") (pinfunction "IOR_160_101") (pintype "bidirectional"))
      (node (ref "U$1") (pin "51") (pinfunction "D5_A_51") (pintype "bidirectional"))
    )
    (net (code "23") (name "/D5B") (class "Default")
      (node (ref "IC3") (pin "115") (pinfunction "IOT_172_115") (pintype "bidirectional"))
      (node (ref "U$1") (pin "34") (pinfunction "D5_B_34") (pintype "bidirectional"))
    )
    (net (code "24") (name "/D6A") (class "Default")
      (node (ref "IC3") (pin "99") (pinfunction "IOR_152_99") (pintype "bidirectional"))
      (node (ref "U$1") (pin "54") (pinfunction "D6_A_54") (pintype "bidirectional"))
    )
    (net (code "25") (name "/D6B") (class "Default")
      (node (ref "IC3") (pin "114") (pinfunction "IOT_171_114") (pintype "bidirectional"))
      (node (ref "U$1") (pin "35") (pinfunction "D6_B_35") (pintype "bidirectional"))
    )
    (net (code "26") (name "/D7A") (class "Default")
      (node (ref "IC3") (pin "98") (pinfunction "IOR_148_98") (pintype "bidirectional"))
      (node (ref "U$1") (pin "55") (pinfunction "D7_A_55") (pintype "bidirectional"))
    )
    (net (code "27") (name "/D7B") (class "Default")
      (node (ref "IC3") (pin "113") (pinfunction "IOT_170_113") (pintype "bidirectional"))
      (node (ref "U$1") (pin "36") (pinfunction "D7_B_36") (pintype "bidirectional"))
    )
    (net (code "28") (name "/D8A") (class "Default")
      (node (ref "IC3") (pin "97") (pinfunction "IOR_147_97") (pintype "bidirectional"))
      (node (ref "U$1") (pin "56") (pinfunction "D8_A_56") (pintype "bidirectional"))
    )
    (net (code "29") (name "/D8B") (class "Default")
      (node (ref "IC3") (pin "112") (pinfunction "IOT_169_112") (pintype "bidirectional"))
      (node (ref "U$1") (pin "37") (pinfunction "D8_B_37") (pintype "bidirectional"))
    )
    (net (code "30") (name "/D9A") (class "Default")
      (node (ref "IC3") (pin "96") (pinfunction "IOR_146_96") (pintype "bidirectional"))
      (node (ref "U$1") (pin "57") (pinfunction "D9_A(MSB)_57") (pintype "bidirectional"))
    )
    (net (code "31") (name "/D9B") (class "Default")
      (node (ref "IC3") (pin "110") (pinfunction "IOT_168_110") (pintype "bidirectional"))
      (node (ref "U$1") (pin "38") (pinfunction "D9_B(MSB)_38") (pintype "bidirectional"))
    )
    (net (code "32") (name "/DHT11_DATA") (class "Default")
      (node (ref "PI_GPIO") (pin "38") (pinfunction "38_38") (pintype "passive"))
      (node (ref "R32") (pin "2") (pinfunction "2_2") (pintype "passive"))
      (node (ref "U7") (pin "2") (pinfunction "DATA_2") (pintype "bidirectional"))
    )
    (net (code "33") (name "/DONE") (class "Default")
      (node (ref "IC3") (pin "65") (pinfunction "CDONE_65") (pintype "bidirectional"))
      (node (ref "PI_GPIO") (pin "13") (pinfunction "13_13") (pintype "passive"))
      (node (ref "R49") (pin "1") (pinfunction "1_1") (pintype "passive"))
    )
    (net (code "34") (name "/FPGA1A") (class "Default")
      (node (ref "IC3") (pin "11") (pinfunction "IOL_8A_11") (pintype "bidirectional"))
      (node (ref "X1") (pin "1") (pinfunction "S_1") (pintype "passive"))
    )
    (net (code "35") (name "/FPGA1B") (class "Default")
      (node (ref "IC3") (pin "134") (pinfunction "IOT_212_134") (pintype "bidirectional"))
      (node (ref "X2") (pin "1") (pinfunction "S_1") (pintype "passive"))
    )
    (net (code "36") (name "/FPGA2A") (class "Default")
      (node (ref "IC3") (pin "12") (pinfunction "IOL_8B_12") (pintype "bidirectional"))
      (node (ref "X1") (pin "2") (pinfunction "S_2") (pintype "passive"))
    )
    (net (code "37") (name "/FPGA2B") (class "Default")
      (node (ref "IC3") (pin "135") (pinfunction "IOT_213_135") (pintype "bidirectional"))
      (node (ref "X2") (pin "2") (pinfunction "S_2") (pintype "passive"))
    )
    (net (code "38") (name "/FPGA3A") (class "Default")
      (node (ref "IC3") (pin "15") (pinfunction "IOL_10A_15") (pintype "bidirectional"))
      (node (ref "X1") (pin "3") (pinfunction "S_3") (pintype "passive"))
    )
    (net (code "39") (name "/FPGA3B") (class "Default")
      (node (ref "IC3") (pin "136") (pinfunction "IOT_214_136") (pintype "bidirectional"))
      (node (ref "X2") (pin "3") (pinfunction "S_3") (pintype "passive"))
    )
    (net (code "40") (name "/FPGA4A") (class "Default")
      (node (ref "IC3") (pin "16") (pinfunction "IOL_10B_16") (pintype "bidirectional"))
      (node (ref "X1") (pin "4") (pinfunction "S_4") (pintype "passive"))
    )
    (net (code "41") (name "/FPGA4B") (class "Default")
      (node (ref "IC3") (pin "137") (pinfunction "IOT_215_137") (pintype "bidirectional"))
      (node (ref "X2") (pin "4") (pinfunction "S_4") (pintype "passive"))
    )
    (net (code "42") (name "/FPGA5A") (class "Default")
      (node (ref "IC3") (pin "17") (pinfunction "IOL_12A_17") (pintype "bidirectional"))
      (node (ref "X1") (pin "5") (pinfunction "S_5") (pintype "passive"))
    )
    (net (code "43") (name "/FPGA5B") (class "Default")
      (node (ref "IC3") (pin "138") (pinfunction "IOT_216_138") (pintype "bidirectional"))
      (node (ref "X2") (pin "5") (pinfunction "S_5") (pintype "passive"))
    )
    (net (code "44") (name "/FPGA6A") (class "Default")
      (node (ref "IC3") (pin "18") (pinfunction "IOL_12B_18") (pintype "bidirectional"))
      (node (ref "X1") (pin "6") (pinfunction "S_6") (pintype "passive"))
    )
    (net (code "45") (name "/FPGA6B") (class "Default")
      (node (ref "IC3") (pin "139") (pinfunction "IOT_217_139") (pintype "bidirectional"))
      (node (ref "X2") (pin "6") (pinfunction "S_6") (pintype "passive"))
    )
    (net (code "46") (name "/FPGA7A") (class "Default")
      (node (ref "IC3") (pin "19") (pinfunction "IOL_13A_19") (pintype "bidirectional"))
      (node (ref "X1") (pin "7") (pinfunction "S_7") (pintype "passive"))
    )
    (net (code "47") (name "/FPGA7B") (class "Default")
      (node (ref "IC3") (pin "141") (pinfunction "IOT_219_141") (pintype "bidirectional"))
      (node (ref "X2") (pin "7") (pinfunction "S_7") (pintype "passive"))
    )
    (net (code "48") (name "/FPGA8A") (class "Default")
      (node (ref "IC3") (pin "21") (pinfunction "IOL_14A_GBIN6_21") (pintype "bidirectional"))
      (node (ref "X1") (pin "8") (pinfunction "S_8") (pintype "passive"))
    )
    (net (code "49") (name "/FPGA8B") (class "Default")
      (node (ref "IC3") (pin "142") (pinfunction "IOT_220_142") (pintype "bidirectional"))
      (node (ref "X2") (pin "8") (pinfunction "S_8") (pintype "passive"))
    )
    (net (code "50") (name "/FPGA9A") (class "Default")
      (node (ref "IC3") (pin "22") (pinfunction "IOL_14B_22") (pintype "bidirectional"))
      (node (ref "X1") (pin "9") (pinfunction "S_9") (pintype "passive"))
    )
    (net (code "51") (name "/FPGA9B") (class "Default")
      (node (ref "IC3") (pin "143") (pinfunction "IOT_221_143") (pintype "bidirectional"))
      (node (ref "X2") (pin "9") (pinfunction "S_9") (pintype "passive"))
    )
    (net (code "52") (name "/FPGA10A") (class "Default")
      (node (ref "IC3") (pin "23") (pinfunction "IOL_17A_23") (pintype "bidirectional"))
      (node (ref "X1") (pin "10") (pinfunction "S_10") (pintype "passive"))
    )
    (net (code "53") (name "/FPGA10B") (class "Default")
      (node (ref "IC3") (pin "144") (pinfunction "IOT_222_144") (pintype "bidirectional"))
      (node (ref "X2") (pin "10") (pinfunction "S_10") (pintype "passive"))
    )
    (net (code "54") (name "/FPGA11A") (class "Default")
      (node (ref "IC3") (pin "24") (pinfunction "IOL_17B_24") (pintype "bidirectional"))
      (node (ref "X1") (pin "11") (pinfunction "S_11") (pintype "passive"))
    )
    (net (code "55") (name "/FPGA11B") (class "Default")
      (node (ref "IC3") (pin "1") (pinfunction "IOL_2A_1") (pintype "bidirectional"))
      (node (ref "X2") (pin "11") (pinfunction "S_11") (pintype "passive"))
    )
    (net (code "56") (name "/FPGA12A") (class "Default")
      (node (ref "IC3") (pin "25") (pinfunction "IOL_18_A_25") (pintype "bidirectional"))
      (node (ref "X1") (pin "12") (pinfunction "S_12") (pintype "passive"))
    )
    (net (code "57") (name "/FPGA12B") (class "Default")
      (node (ref "IC3") (pin "2") (pinfunction "IOL_2B_2") (pintype "bidirectional"))
      (node (ref "X2") (pin "12") (pinfunction "S_12") (pintype "passive"))
    )
    (net (code "58") (name "/GPS_PPS") (class "Default")
      (node (ref "R33") (pin "1") (pinfunction "1_1") (pintype "passive"))
      (node (ref "U6") (pin "4") (pinfunction "1PPS_4") (pintype "bidirectional"))
    )
    (net (code "59") (name "/ID_SC") (class "Default")
      (node (ref "PI_GPIO") (pin "28") (pinfunction "28_28") (pintype "passive"))
      (node (ref "U4") (pin "1") (pinfunction "SCL_1") (pintype "bidirectional"))
    )
    (net (code "60") (name "/ID_SD") (class "Default")
      (node (ref "PI_GPIO") (pin "27") (pinfunction "27_27") (pintype "passive"))
      (node (ref "U4") (pin "3") (pinfunction "SDA_3") (pintype "bidirectional"))
    )
    (net (code "61") (name "/IMU_ADDR") (class "Default")
      (node (ref "J4") (pin "1") (pinfunction "1_1") (pintype "bidirectional"))
      (node (ref "R42") (pin "1") (pinfunction "1_1") (pintype "passive"))
      (node (ref "U3") (pin "9") (pinfunction "AD0/SDO_9") (pintype "bidirectional"))
    )
    (net (code "62") (name "/IMU_INT") (class "Default")
      (node (ref "PI_GPIO") (pin "16") (pinfunction "16_16") (pintype "passive"))
      (node (ref "U3") (pin "12") (pinfunction "INT_12") (pintype "bidirectional"))
    )
    (net (code "63") (name "/LEDB") (class "Default")
      (node (ref "IC3") (pin "83") (pinfunction "IOR_119_83") (pintype "bidirectional"))
      (node (ref "PI_GPIO") (pin "37") (pinfunction "37_37") (pintype "passive"))
      (node (ref "R47") (pin "2") (pinfunction "2_2") (pintype "passive"))
    )
    (net (code "64") (name "/MISO") (class "Default")
      (node (ref "IC3") (pin "67") (pinfunction "IOB_105_SDO_67") (pintype "bidirectional"))
      (node (ref "J9") (pin "3") (pinfunction "3_3") (pintype "bidirectional"))
      (node (ref "PI_GPIO") (pin "21") (pinfunction "21_21") (pintype "passive"))
    )
    (net (code "65") (name "/MOSI") (class "Default")
      (node (ref "IC3") (pin "68") (pinfunction "IOB_106_SDI_68") (pintype "bidirectional"))
      (node (ref "J9") (pin "2") (pinfunction "2_2") (pintype "bidirectional"))
      (node (ref "PI_GPIO") (pin "19") (pinfunction "19_19") (pintype "passive"))
    )
    (net (code "66") (name "/N$44") (class "Default")
      (node (ref "U3") (pin "21") (pinfunction "AUX_DA_21") (pintype "bidirectional"))
    )
    (net (code "67") (name "/N$45") (class "Default")
      (node (ref "U3") (pin "7") (pinfunction "AUX_CL_7") (pintype "bidirectional"))
    )
    (net (code "68") (name "/PI3V3") (class "Default")
      (node (ref "PI_GPIO") (pin "1") (pinfunction "1_1") (pintype "passive"))
    )
    (net (code "69") (name "/PILED1") (class "Default")
      (node (ref "PI_GPIO") (pin "35") (pinfunction "35_35") (pintype "passive"))
      (node (ref "R43") (pin "2") (pinfunction "2_2") (pintype "passive"))
    )
    (net (code "70") (name "/PILED2") (class "Default")
      (node (ref "PI_GPIO") (pin "36") (pinfunction "36_36") (pintype "passive"))
      (node (ref "R45") (pin "2") (pinfunction "2_2") (pintype "passive"))
    )
    (net (code "71") (name "/PIX1") (class "Default")
      (node (ref "IC3") (pin "93") (pinfunction "IOR_140_GBIN3_93") (pintype "bidirectional"))
      (node (ref "PI_GPIO") (pin "12") (pinfunction "12_12") (pintype "passive"))
    )
    (net (code "72") (name "/PIX2") (class "Default")
      (node (ref "IC3") (pin "48") (pinfunction "IOB_80_48") (pintype "bidirectional"))
      (node (ref "PI_GPIO") (pin "40") (pinfunction "40_40") (pintype "passive"))
    )
    (net (code "73") (name "/PIX3") (class "Default")
      (node (ref "IC3") (pin "39") (pinfunction "IOB_61_39") (pintype "bidirectional"))
      (node (ref "PI_GPIO") (pin "18") (pinfunction "18_18") (pintype "passive"))
    )
    (net (code "74") (name "/PIX4") (class "Default")
      (node (ref "IC3") (pin "41") (pinfunction "IOB_63_41") (pintype "bidirectional"))
      (node (ref "PI_GPIO") (pin "22") (pinfunction "22_22") (pintype "passive"))
    )
    (net (code "75") (name "/PIX5") (class "Default")
      (node (ref "IC3") (pin "42") (pinfunction "IOB_64_42") (pintype "bidirectional"))
    )
    (net (code "76") (name "/PIX6") (class "Default")
      (node (ref "IC3") (pin "43") (pinfunction "IOB_71_43") (pintype "bidirectional"))
      (node (ref "PI_GPIO") (pin "29") (pinfunction "29_29") (pintype "passive"))
    )
    (net (code "77") (name "/PIX7") (class "Default")
      (node (ref "IC3") (pin "44") (pinfunction "IOB_72_44") (pintype "bidirectional"))
      (node (ref "PI_GPIO") (pin "31") (pinfunction "31_31") (pintype "passive"))
    )
    (net (code "78") (name "/PIX8") (class "Default")
      (node (ref "IC3") (pin "45") (pinfunction "IOB_73_45") (pintype "bidirectional"))
    )
    (net (code "79") (name "/PIX9") (class "Default")
      (node (ref "IC3") (pin "47") (pinfunction "IOB_79_47") (pintype "bidirectional"))
      (node (ref "PI_GPIO") (pin "33") (pinfunction "33_33") (pintype "passive"))
    )
    (net (code "80") (name "/PRESS_ADDR") (class "Default")
      (node (ref "J3") (pin "1") (pinfunction "1_1") (pintype "bidirectional"))
      (node (ref "R37") (pin "1") (pinfunction "1_1") (pintype "passive"))
      (node (ref "U5") (pin "5") (pinfunction "SDO_5") (pintype "bidirectional"))
    )
    (net (code "81") (name "/PWRRST") (class "Default")
      (node (ref "J9") (pin "6") (pinfunction "6_6") (pintype "bidirectional"))
      (node (ref "PI_GPIO") (pin "32") (pinfunction "32_32") (pintype "passive"))
    )
    (net (code "82") (name "/REGOUT") (class "Default")
      (node (ref "C47") (pin "2") (pinfunction "2_2") (pintype "passive"))
      (node (ref "U3") (pin "10") (pinfunction "REGOUT_10") (pintype "bidirectional"))
    )
    (net (code "83") (name "/RESET") (class "Default")
      (node (ref "IC3") (pin "66") (pinfunction "CRESET_B_66") (pintype "bidirectional"))
      (node (ref "PI_GPIO") (pin "15") (pinfunction "15_15") (pintype "passive"))
      (node (ref "R48") (pin "1") (pinfunction "1_1") (pintype "passive"))
    )
    (net (code "84") (name "/RXD_PI") (class "Default")
      (node (ref "PI_GPIO") (pin "10") (pinfunction "10_10") (pintype "passive"))
      (node (ref "U6") (pin "2") (pinfunction "TXD1_2") (pintype "bidirectional"))
    )
    (net (code "85") (name "/SCK") (class "Default")
      (node (ref "IC3") (pin "70") (pinfunction "IOB_107_SCK_70") (pintype "bidirectional"))
      (node (ref "J9") (pin "4") (pinfunction "4_4") (pintype "bidirectional"))
      (node (ref "PI_GPIO") (pin "23") (pinfunction "23_23") (pintype "passive"))
      (node (ref "R50") (pin "1") (pinfunction "1_1") (pintype "passive"))
    )
    (net (code "86") (name "/SCL1") (class "Default")
      (node (ref "PI_GPIO") (pin "5") (pinfunction "5_5") (pintype "passive"))
      (node (ref "R41") (pin "2") (pinfunction "2_2") (pintype "passive"))
      (node (ref "U3") (pin "23") (pinfunction "SCL/SCLK_23") (pintype "bidirectional"))
      (node (ref "U5") (pin "4") (pinfunction "SCK_4") (pintype "bidirectional"))
    )
    (net (code "87") (name "/SDA1") (class "Default")
      (node (ref "PI_GPIO") (pin "3") (pinfunction "3_3") (pintype "passive"))
      (node (ref "R40") (pin "2") (pinfunction "2_2") (pintype "passive"))
      (node (ref "U3") (pin "24") (pinfunction "SDA/SDI_24") (pintype "bidirectional"))
      (node (ref "U5") (pin "3") (pinfunction "SDI_3") (pintype "bidirectional"))
    )
    (net (code "88") (name "/TEMPA") (class "Default")
      (node (ref "J6") (pin "1") (pinfunction "1_1") (pintype "bidirectional"))
      (node (ref "J8") (pin "1") (pinfunction "1_1") (pintype "bidirectional"))
    )
    (net (code "89") (name "/TEMPB") (class "Default")
      (node (ref "J6") (pin "2") (pinfunction "2_2") (pintype "bidirectional"))
      (node (ref "J8") (pin "2") (pinfunction "2_2") (pintype "bidirectional"))
    )
    (net (code "90") (name "/TXD_PI") (class "Default")
      (node (ref "PI_GPIO") (pin "8") (pinfunction "8_8") (pintype "passive"))
      (node (ref "U6") (pin "3") (pinfunction "RXD1_3") (pintype "bidirectional"))
    )
    (net (code "91") (name "/VBIAS1") (class "Default")
      (node (ref "J2") (pin "3") (pinfunction "P$3_3") (pintype "bidirectional"))
      (node (ref "J7") (pin "3") (pinfunction "P$3_3") (pintype "bidirectional"))
    )
    (net (code "92") (name "/VBIAS2") (class "Default")
      (node (ref "J2") (pin "4") (pinfunction "P$4_4") (pintype "bidirectional"))
      (node (ref "J7") (pin "4") (pinfunction "P$4_4") (pintype "bidirectional"))
    )
    (net (code "93") (name "/VBUS") (class "Default")
      (node (ref "D2") (pin "+") (pinfunction "+_+") (pintype "passive"))
      (node (ref "USB1") (pin "1") (pinfunction "VCC_1") (pintype "bidirectional"))
    )
    (net (code "94") (name "/VIN+A") (class "Default")
      (node (ref "C30") (pin "2") (pinfunction "2_2") (pintype "passive"))
      (node (ref "R16") (pin "2") (pinfunction "2_2") (pintype "passive"))
      (node (ref "U$1") (pin "2") (pinfunction "VIN+_A_2") (pintype "bidirectional"))
    )
    (net (code "95") (name "/VIN+B") (class "Default")
      (node (ref "C34") (pin "2") (pinfunction "2_2") (pintype "passive"))
      (node (ref "R26") (pin "2") (pinfunction "2_2") (pintype "passive"))
      (node (ref "U$1") (pin "15") (pinfunction "VIN+_B_15") (pintype "bidirectional"))
    )
    (net (code "96") (name "/VIN-A") (class "Default")
      (node (ref "C30") (pin "1") (pinfunction "1_1") (pintype "passive"))
      (node (ref "R19") (pin "2") (pinfunction "2_2") (pintype "passive"))
      (node (ref "U$1") (pin "3") (pinfunction "VIN-_A_3") (pintype "bidirectional"))
    )
    (net (code "97") (name "/VIN-B") (class "Default")
      (node (ref "C34") (pin "1") (pinfunction "1_1") (pintype "passive"))
      (node (ref "R29") (pin "2") (pinfunction "2_2") (pintype "passive"))
      (node (ref "U$1") (pin "14") (pinfunction "VIN-_B_14") (pintype "bidirectional"))
    )
    (net (code "98") (name "/~{SS}") (class "Default")
      (node (ref "IC3") (pin "71") (pinfunction "IOB_108_SS_71") (pintype "bidirectional"))
      (node (ref "PI_GPIO") (pin "24") (pinfunction "24_24") (pintype "passive"))
      (node (ref "R35") (pin "2") (pinfunction "2_2") (pintype "passive"))
    )
    (net (code "99") (name "5V") (class "Default")
      (node (ref "5V") (pin "TP") (pinfunction "TP_TP") (pintype "input"))
      (node (ref "C20") (pin "1") (pinfunction "1_1") (pintype "passive"))
      (node (ref "C9") (pin "2") (pinfunction "2_2") (pintype "passive"))
      (node (ref "D1") (pin "+") (pinfunction "+_+") (pintype "passive"))
      (node (ref "F2") (pin "P$2") (pinfunction "P$2_P$2") (pintype "passive"))
      (node (ref "U2") (pin "3") (pinfunction "IN_3") (pintype "bidirectional"))
      (node (ref "U8") (pin "1") (pinfunction "EN_1") (pintype "bidirectional"))
      (node (ref "U8") (pin "4") (pinfunction "IN_4") (pintype "bidirectional"))
    )
    (net (code "100") (name "DGND") (class "Default")
      (node (ref "C1") (pin "+") (pinfunction "+_+") (pintype "passive"))
      (node (ref "C10") (pin "1") (pinfunction "1_1") (pintype "passive"))
      (node (ref "C11") (pin "2") (pinfunction "2_2") (pintype "passive"))
      (node (ref "C12") (pin "2") (pinfunction "2_2") (pintype "passive"))
      (node (ref "C13") (pin "2") (pinfunction "2_2") (pintype "passive"))
      (node (ref "C14") (pin "2") (pinfunction "2_2") (pintype "passive"))
      (node (ref "C15") (pin "1") (pinfunction "1_1") (pintype "passive"))
      (node (ref "C18") (pin "1") (pinfunction "1_1") (pintype "passive"))
      (node (ref "C2") (pin "1") (pinfunction "1_1") (pintype "passive"))
      (node (ref "C20") (pin "2") (pinfunction "2_2") (pintype "passive"))
      (node (ref "C22") (pin "1") (pinfunction "1_1") (pintype "passive"))
      (node (ref "C23") (pin "2") (pinfunction "2_2") (pintype "passive"))
      (node (ref "C24") (pin "1") (pinfunction "1_1") (pintype "passive"))
      (node (ref "C25") (pin "1") (pinfunction "1_1") (pintype "passive"))
      (node (ref "C26") (pin "1") (pinfunction "1_1") (pintype "passive"))
      (node (ref "C27") (pin "1") (pinfunction "1_1") (pintype "passive"))
      (node (ref "C28") (pin "1") (pinfunction "1_1") (pintype "passive"))
      (node (ref "C29") (pin "1") (pinfunction "1_1") (pintype "passive"))
      (node (ref "C3") (pin "2") (pinfunction "2_2") (pintype "passive"))
      (node (ref "C31") (pin "1") (pinfunction "1_1") (pintype "passive"))
      (node (ref "C32") (pin "1") (pinfunction "1_1") (pintype "passive"))
      (node (ref "C33") (pin "1") (pinfunction "1_1") (pintype "passive"))
      (node (ref "C35") (pin "2") (pinfunction "2_2") (pintype "passive"))
      (node (ref "C37") (pin "2") (pinfunction "2_2") (pintype "passive"))
      (node (ref "C38") (pin "2") (pinfunction "2_2") (pintype "passive"))
      (node (ref "C39") (pin "1") (pinfunction "1_1") (pintype "passive"))
      (node (ref "C4") (pin "2") (pinfunction "2_2") (pintype "passive"))
      (node (ref "C40") (pin "2") (pinfunction "2_2") (pintype "passive"))
      (node (ref "C41") (pin "1") (pinfunction "1_1") (pintype "passive"))
      (node (ref "C42") (pin "1") (pinfunction "1_1") (pintype "passive"))
      (node (ref "C43") (pin "1") (pinfunction "1_1") (pintype "passive"))
      (node (ref "C44") (pin "1") (pinfunction "1_1") (pintype "passive"))
      (node (ref "C45") (pin "1") (pinfunction "1_1") (pintype "passive"))
      (node (ref "C46") (pin "1") (pinfunction "1_1") (pintype "passive"))
      (node (ref "C47") (pin "1") (pinfunction "1_1") (pintype "passive"))
      (node (ref "C48") (pin "1") (pinfunction "1_1") (pintype "passive"))
      (node (ref "C49") (pin "2") (pinfunction "2_2") (pintype "passive"))
      (node (ref "C5") (pin "1") (pinfunction "1_1") (pintype "passive"))
      (node (ref "C50") (pin "2") (pinfunction "2_2") (pintype "passive"))
      (node (ref "C51") (pin "2") (pinfunction "2_2") (pintype "passive"))
      (node (ref "C52") (pin "2") (pinfunction "2_2") (pintype "passive"))
      (node (ref "C56") (pin "2") (pinfunction "2_2") (pintype "passive"))
      (node (ref "C6") (pin "1") (pinfunction "1_1") (pintype "passive"))
      (node (ref "C60") (pin "1") (pinfunction "1_1") (pintype "passive"))
      (node (ref "C7") (pin "2") (pinfunction "2_2") (pintype "passive"))
      (node (ref "C8") (pin "2") (pinfunction "2_2") (pintype "passive"))
      (node (ref "C9") (pin "1") (pinfunction "1_1") (pintype "passive"))
      (node (ref "D3") (pin "-") (pinfunction "-_-") (pintype "passive"))
      (node (ref "D4") (pin "-") (pinfunction "-_-") (pintype "passive"))
      (node (ref "D5") (pin "-") (pinfunction "-_-") (pintype "passive"))
      (node (ref "D6") (pin "-") (pinfunction "-_-") (pintype "passive"))
      (node (ref "D7") (pin "-") (pinfunction "-_-") (pintype "passive"))
      (node (ref "IC3") (pin "103") (pinfunction "GND_103") (pintype "bidirectional"))
      (node (ref "IC3") (pin "13") (pinfunction "GND_13") (pintype "bidirectional"))
      (node (ref "IC3") (pin "132") (pinfunction "GND_132") (pintype "bidirectional"))
      (node (ref "IC3") (pin "14") (pinfunction "GND_14") (pintype "bidirectional"))
      (node (ref "IC3") (pin "140") (pinfunction "GND_140") (pintype "bidirectional"))
      (node (ref "IC3") (pin "5") (pinfunction "GND_5") (pintype "bidirectional"))
      (node (ref "IC3") (pin "59") (pinfunction "GND_59") (pintype "bidirectional"))
      (node (ref "IC3") (pin "69") (pinfunction "GND_69") (pintype "bidirectional"))
      (node (ref "IC3") (pin "86") (pinfunction "GND_86") (pintype "bidirectional"))
      (node (ref "J1") (pin "2") (pinfunction "P$2_2") (pintype "bidirectional"))
      (node (ref "J2") (pin "2") (pinfunction "P$2_2") (pintype "bidirectional"))
      (node (ref "J5") (pin "1") (pinfunction "GND_1") (pintype "passive"))
      (node (ref "J7") (pin "2") (pinfunction "P$2_2") (pintype "bidirectional"))
      (node (ref "PI_GPIO") (pin "14") (pinfunction "14_14") (pintype "passive"))
      (node (ref "PI_GPIO") (pin "20") (pinfunction "20_20") (pintype "passive"))
      (node (ref "PI_GPIO") (pin "25") (pinfunction "25_25") (pintype "passive"))
      (node (ref "PI_GPIO") (pin "30") (pinfunction "30_30") (pintype "passive"))
      (node (ref "PI_GPIO") (pin "34") (pinfunction "34_34") (pintype "passive"))
      (node (ref "PI_GPIO") (pin "39") (pinfunction "39_39") (pintype "passive"))
      (node (ref "PI_GPIO") (pin "6") (pinfunction "6_6") (pintype "passive"))
      (node (ref "PI_GPIO") (pin "9") (pinfunction "9_9") (pintype "passive"))
      (node (ref "R12") (pin "2") (pinfunction "2_2") (pintype "passive"))
      (node (ref "R13") (pin "1") (pinfunction "1_1") (pintype "passive"))
      (node (ref "R17") (pin "1") (pinfunction "1_1") (pintype "passive"))
      (node (ref "R21") (pin "2") (pinfunction "2_2") (pintype "passive"))
      (node (ref "R22") (pin "2") (pinfunction "2_2") (pintype "passive"))
      (node (ref "R23") (pin "1") (pinfunction "1_1") (pintype "passive"))
      (node (ref "R27") (pin "1") (pinfunction "1_1") (pintype "passive"))
      (node (ref "R31") (pin "2") (pinfunction "2_2") (pintype "passive"))
      (node (ref "R37") (pin "2") (pinfunction "2_2") (pintype "passive"))
      (node (ref "R4") (pin "2") (pinfunction "2_2") (pintype "passive"))
      (node (ref "R42") (pin "2") (pinfunction "2_2") (pintype "passive"))
      (node (ref "R5") (pin "2") (pinfunction "2_2") (pintype "passive"))
      (node (ref "R51") (pin "2") (pinfunction "2_2") (pintype "passive"))
      (node (ref "R53") (pin "1") (pinfunction "1_1") (pintype "passive"))
      (node (ref "R54") (pin "2") (pinfunction "2_2") (pintype "passive"))
      (node (ref "R6") (pin "2") (pinfunction "2_2") (pintype "passive"))
      (node (ref "R7") (pin "2") (pinfunction "2_2") (pintype "passive"))
      (node (ref "R8") (pin "2") (pinfunction "2_2") (pintype "passive"))
      (node (ref "R9") (pin "2") (pinfunction "2_2") (pintype "passive"))
      (node (ref "U$1") (pin "1") (pinfunction "AGND$1_1") (pintype "bidirectional"))
      (node (ref "U$1") (pin "13") (pinfunction "AGND$3_13") (pintype "bidirectional"))
      (node (ref "U$1") (pin "16") (pinfunction "AGND$4_16") (pintype "bidirectional"))
      (node (ref "U$1") (pin "28") (pinfunction "DRGND$1_28") (pintype "bidirectional"))
      (node (ref "U$1") (pin "4") (pinfunction "AGND$2_4") (pintype "bidirectional"))
      (node (ref "U$1") (pin "40") (pinfunction "DRGND$2_40") (pintype "bidirectional"))
      (node (ref "U$1") (pin "52") (pinfunction "DRGND$3_52") (pintype "bidirectional"))
      (node (ref "U$1") (pin "65") (pinfunction "EPAD_65") (pintype "bidirectional"))
      (node (ref "U$1") (pin "9") (pinfunction "SENSE_9") (pintype "bidirectional"))
      (node (ref "U$16") (pin "P$1") (pinfunction "P_P$1") (pintype "bidirectional"))
      (node (ref "U$2") (pin "6") (pinfunction "V-_6") (pintype "bidirectional"))
      (node (ref "U$21") (pin "P$1") (pinfunction "P_P$1") (pintype "bidirectional"))
      (node (ref "U$22") (pin "P$1") (pinfunction "P_P$1") (pintype "bidirectional"))
      (node (ref "U$24") (pin "P$1") (pinfunction "P_P$1") (pintype "bidirectional"))
      (node (ref "U$3") (pin "6") (pinfunction "V-_6") (pintype "bidirectional"))
      (node (ref "U1") (pin "P$1") (pinfunction "OEN_P$1") (pintype "bidirectional"))
      (node (ref "U1") (pin "P$2") (pinfunction "GND_P$2") (pintype "power_in"))
      (node (ref "U2") (pin "1") (pinfunction "GND_1") (pintype "bidirectional"))
      (node (ref "U3") (pin "11") (pinfunction "FSYNC_11") (pintype "bidirectional"))
      (node (ref "U3") (pin "18") (pinfunction "GND_18") (pintype "bidirectional"))
      (node (ref "U3") (pin "20") (pinfunction "RESV_20") (pintype "bidirectional"))
      (node (ref "U4") (pin "2") (pinfunction "GND_2") (pintype "power_in"))
      (node (ref "U4") (pin "5") (pinfunction "WP_5") (pintype "bidirectional"))
      (node (ref "U5") (pin "1") (pinfunction "GND_1") (pintype "bidirectional"))
      (node (ref "U5") (pin "7") (pinfunction "GND_7") (pintype "bidirectional"))
      (node (ref "U6") (pin "1") (pinfunction "GND_1") (pintype "bidirectional"))
      (node (ref "U6") (pin "10") (pinfunction "GND_10") (pintype "bidirectional"))
      (node (ref "U6") (pin "12") (pinfunction "GND_12") (pintype "bidirectional"))
      (node (ref "U6") (pin "18") (pinfunction "TIMER_18") (pintype "bidirectional"))
      (node (ref "U7") (pin "4") (pinfunction "GND_4") (pintype "power_in"))
      (node (ref "U8") (pin "2") (pinfunction "GND_2") (pintype "bidirectional"))
      (node (ref "USB1") (pin "5") (pinfunction "GND_5") (pintype "bidirectional"))
    )
    (net (code "101") (name "Net-(C1-Pad-)") (class "Default")
      (node (ref "C1") (pin "-") (pinfunction "-_-") (pintype "passive"))
      (node (ref "L2") (pin "1") (pinfunction "1_1") (pintype "passive"))
      (node (ref "U2") (pin "2") (pinfunction "OUT_2") (pintype "bidirectional"))
      (node (ref "U2") (pin "TER") (pinfunction "OUT_TER") (pintype "bidirectional"))
    )
    (net (code "102") (name "Net-(C11-Pad1)") (class "Default")
      (node (ref "C11") (pin "1") (pinfunction "1_1") (pintype "passive"))
      (node (ref "IC3") (pin "89") (pinfunction "VCCIO_89") (pintype "bidirectional"))
    )
    (net (code "103") (name "Net-(C39-Pad2)") (class "Default")
      (node (ref "C39") (pin "2") (pinfunction "2_2") (pintype "passive"))
      (node (ref "R22") (pin "1") (pinfunction "1_1") (pintype "passive"))
      (node (ref "USB1") (pin "S1") (pinfunction "GND_S1") (pintype "bidirectional"))
      (node (ref "USB1") (pin "S2") (pinfunction "GND_S2") (pintype "bidirectional"))
      (node (ref "USB1") (pin "S3") (pinfunction "GND_S3") (pintype "bidirectional"))
      (node (ref "USB1") (pin "S4") (pinfunction "GND_S4") (pintype "bidirectional"))
      (node (ref "USB1") (pin "S5") (pinfunction "GND_S5") (pintype "bidirectional"))
      (node (ref "USB1") (pin "S6") (pinfunction "GND_S6") (pintype "bidirectional"))
    )
    (net (code "104") (name "Net-(D2-Pad-)") (class "Default")
      (node (ref "D2") (pin "-") (pinfunction "-_-") (pintype "passive"))
      (node (ref "F2") (pin "P$1") (pinfunction "P$1_P$1") (pintype "passive"))
    )
    (net (code "105") (name "Net-(D3-Pad+)") (class "Default")
      (node (ref "D3") (pin "+") (pinfunction "+_+") (pintype "passive"))
      (node (ref "R1") (pin "2") (pinfunction "2_2") (pintype "passive"))
    )
    (net (code "106") (name "Net-(D4-Pad+)") (class "Default")
      (node (ref "D4") (pin "+") (pinfunction "+_+") (pintype "passive"))
      (node (ref "R2") (pin "1") (pinfunction "1_1") (pintype "passive"))
    )
    (net (code "107") (name "Net-(D5-Pad+)") (class "Default")
      (node (ref "D5") (pin "+") (pinfunction "+_+") (pintype "passive"))
      (node (ref "R43") (pin "1") (pinfunction "1_1") (pintype "passive"))
    )
    (net (code "108") (name "Net-(D6-Pad+)") (class "Default")
      (node (ref "D6") (pin "+") (pinfunction "+_+") (pintype "passive"))
      (node (ref "R45") (pin "1") (pinfunction "1_1") (pintype "passive"))
    )
    (net (code "109") (name "Net-(D7-Pad+)") (class "Default")
      (node (ref "D7") (pin "+") (pinfunction "+_+") (pintype "passive"))
      (node (ref "R46") (pin "1") (pinfunction "1_1") (pintype "passive"))
    )
    (net (code "110") (name "Net-(IC3-GNDPLL0)") (class "Default")
      (node (ref "C58") (pin "1") (pinfunction "1_1") (pintype "passive"))
      (node (ref "C59") (pin "1") (pinfunction "1_1") (pintype "passive"))
      (node (ref "IC3") (pin "53") (pinfunction "GNDPLL0_53") (pintype "bidirectional"))
      (node (ref "R51") (pin "1") (pinfunction "1_1") (pintype "passive"))
    )
    (net (code "111") (name "Net-(IC3-GNDPLL1)") (class "Default")
      (node (ref "C36") (pin "2") (pinfunction "2_2") (pintype "passive"))
      (node (ref "C55") (pin "2") (pinfunction "2_2") (pintype "passive"))
      (node (ref "IC3") (pin "127") (pinfunction "GNDPLL1_127") (pintype "bidirectional"))
      (node (ref "R54") (pin "1") (pinfunction "1_1") (pintype "passive"))
    )
    (net (code "112") (name "Net-(IC3-IOB_56)") (class "Default")
      (node (ref "IC3") (pin "37") (pinfunction "IOB_56_37") (pintype "bidirectional"))
      (node (ref "R2") (pin "2") (pinfunction "2_2") (pintype "passive"))
    )
    (net (code "113") (name "Net-(IC3-IOB_96)") (class "Default")
      (node (ref "IC3") (pin "61") (pinfunction "IOB_96_61") (pintype "bidirectional"))
      (node (ref "R1") (pin "1") (pinfunction "1_1") (pintype "passive"))
    )
    (net (code "114") (name "Net-(IC3-IOL_13B_GBIN7)") (class "Default")
      (node (ref "IC3") (pin "20") (pinfunction "IOL_13B_GBIN7_20") (pintype "bidirectional"))
      (node (ref "R33") (pin "2") (pinfunction "2_2") (pintype "passive"))
    )
    (net (code "115") (name "Net-(IC3-VCCPLL0)") (class "Default")
      (node (ref "C58") (pin "2") (pinfunction "2_2") (pintype "passive"))
      (node (ref "C59") (pin "2") (pinfunction "2_2") (pintype "passive"))
      (node (ref "IC3") (pin "54") (pinfunction "VCCPLL0_54") (pintype "bidirectional"))
      (node (ref "R38") (pin "1") (pinfunction "1_1") (pintype "passive"))
    )
    (net (code "116") (name "Net-(IC3-VCCPLL1)") (class "Default")
      (node (ref "C36") (pin "1") (pinfunction "1_1") (pintype "passive"))
      (node (ref "C55") (pin "1") (pinfunction "1_1") (pintype "passive"))
      (node (ref "IC3") (pin "126") (pinfunction "VCCPLL1_126") (pintype "bidirectional"))
      (node (ref "R39") (pin "2") (pinfunction "2_2") (pintype "passive"))
    )
    (net (code "117") (name "Net-(J1-P$4)") (class "Default")
      (node (ref "J1") (pin "4") (pinfunction "P$4_4") (pintype "bidirectional"))
      (node (ref "R47") (pin "1") (pinfunction "1_1") (pintype "passive"))
    )
    (net (code "118") (name "Net-(J5-SIG)") (class "Default")
      (node (ref "C50") (pin "1") (pinfunction "1_1") (pintype "passive"))
      (node (ref "J5") (pin "5") (pinfunction "SIG_5") (pintype "passive"))
      (node (ref "L1") (pin "P$2") (pinfunction "P$2_P$2") (pintype "passive"))
      (node (ref "R34") (pin "2") (pinfunction "2_2") (pintype "passive"))
    )
    (net (code "119") (name "Net-(L1-PadP$1)") (class "Default")
      (node (ref "L1") (pin "P$1") (pinfunction "P$1_P$1") (pintype "passive"))
      (node (ref "R36") (pin "2") (pinfunction "2_2") (pintype "passive"))
    )
    (net (code "120") (name "Net-(U$1-DCS)") (class "Default")
      (node (ref "R3") (pin "1") (pinfunction "1_1") (pintype "passive"))
      (node (ref "U$1") (pin "19") (pinfunction "DCS_19") (pintype "bidirectional"))
    )
    (net (code "121") (name "Net-(U$1-DFS)") (class "Default")
      (node (ref "R4") (pin "1") (pinfunction "1_1") (pintype "passive"))
      (node (ref "U$1") (pin "20") (pinfunction "DFS_20") (pintype "bidirectional"))
    )
    (net (code "122") (name "Net-(U$1-MUX_SELECT)") (class "Default")
      (node (ref "R11") (pin "1") (pinfunction "1_1") (pintype "passive"))
      (node (ref "R12") (pin "1") (pinfunction "1_1") (pintype "passive"))
      (node (ref "U$1") (pin "61") (pinfunction "MUX_SELECT_61") (pintype "bidirectional"))
    )
    (net (code "123") (name "Net-(U$1-OEB_A)") (class "Default")
      (node (ref "R9") (pin "1") (pinfunction "1_1") (pintype "passive"))
      (node (ref "U$1") (pin "59") (pinfunction "OEB_A_59") (pintype "bidirectional"))
    )
    (net (code "124") (name "Net-(U$1-OEB_B)") (class "Default")
      (node (ref "R6") (pin "1") (pinfunction "1_1") (pintype "passive"))
      (node (ref "U$1") (pin "22") (pinfunction "OEB_B_22") (pintype "bidirectional"))
    )
    (net (code "125") (name "Net-(U$1-PDWN_A)") (class "Default")
      (node (ref "R8") (pin "1") (pinfunction "1_1") (pintype "passive"))
      (node (ref "U$1") (pin "60") (pinfunction "PDWN_A_60") (pintype "bidirectional"))
    )
    (net (code "126") (name "Net-(U$1-PDWN_B)") (class "Default")
      (node (ref "R5") (pin "1") (pinfunction "1_1") (pintype "passive"))
      (node (ref "U$1") (pin "21") (pinfunction "PDWN_B_21") (pintype "bidirectional"))
    )
    (net (code "127") (name "Net-(U$1-REFB_A)") (class "Default")
      (node (ref "C18") (pin "2") (pinfunction "2_2") (pintype "passive"))
      (node (ref "C19") (pin "1") (pinfunction "1_1") (pintype "passive"))
      (node (ref "C21") (pin "1") (pinfunction "1_1") (pintype "passive"))
      (node (ref "U$1") (pin "7") (pinfunction "REFB_A_7") (pintype "bidirectional"))
    )
    (net (code "128") (name "Net-(U$1-REFB_B)") (class "Default")
      (node (ref "C16") (pin "2") (pinfunction "2_2") (pintype "passive"))
      (node (ref "C17") (pin "2") (pinfunction "2_2") (pintype "passive"))
      (node (ref "C2") (pin "2") (pinfunction "2_2") (pintype "passive"))
      (node (ref "U$1") (pin "10") (pinfunction "REFB_B_10") (pintype "bidirectional"))
    )
    (net (code "129") (name "Net-(U$1-REFT_A)") (class "Default")
      (node (ref "C15") (pin "2") (pinfunction "2_2") (pintype "passive"))
      (node (ref "C19") (pin "2") (pinfunction "2_2") (pintype "passive"))
      (node (ref "C21") (pin "2") (pinfunction "2_2") (pintype "passive"))
      (node (ref "U$1") (pin "6") (pinfunction "REFT_A_6") (pintype "bidirectional"))
    )
    (net (code "130") (name "Net-(U$1-REFT_B)") (class "Default")
      (node (ref "C16") (pin "1") (pinfunction "1_1") (pintype "passive"))
      (node (ref "C17") (pin "1") (pinfunction "1_1") (pintype "passive"))
      (node (ref "C5") (pin "2") (pinfunction "2_2") (pintype "passive"))
      (node (ref "U$1") (pin "11") (pinfunction "REFT_B_11") (pintype "bidirectional"))
    )
    (net (code "131") (name "Net-(U$1-SHARED_REF)") (class "Default")
      (node (ref "R10") (pin "1") (pinfunction "1_1") (pintype "passive"))
      (node (ref "R7") (pin "1") (pinfunction "1_1") (pintype "passive"))
      (node (ref "U$1") (pin "62") (pinfunction "SHARED_REF_62") (pintype "bidirectional"))
    )
    (net (code "132") (name "Net-(U$1-VREF)") (class "Default")
      (node (ref "C22") (pin "2") (pinfunction "2_2") (pintype "passive"))
      (node (ref "C26") (pin "2") (pinfunction "2_2") (pintype "passive"))
      (node (ref "U$1") (pin "8") (pinfunction "VREF_8") (pintype "bidirectional"))
    )
    (net (code "133") (name "Net-(U$2-+IN)") (class "Default")
      (node (ref "R17") (pin "2") (pinfunction "2_2") (pintype "passive"))
      (node (ref "R18") (pin "1") (pinfunction "1_1") (pintype "passive"))
      (node (ref "U$2") (pin "8") (pinfunction "+IN_8") (pintype "bidirectional"))
    )
    (net (code "134") (name "Net-(U$2-+OUT)") (class "Default")
      (node (ref "R15") (pin "2") (pinfunction "2_2") (pintype "passive"))
      (node (ref "R16") (pin "1") (pinfunction "1_1") (pintype "passive"))
      (node (ref "U$2") (pin "4") (pinfunction "+OUT_4") (pintype "bidirectional"))
    )
    (net (code "135") (name "Net-(U$2--IN)") (class "Default")
      (node (ref "R14") (pin "1") (pinfunction "1_1") (pintype "passive"))
      (node (ref "R15") (pin "1") (pinfunction "1_1") (pintype "passive"))
      (node (ref "U$2") (pin "1") (pinfunction "-IN_1") (pintype "bidirectional"))
    )
    (net (code "136") (name "Net-(U$2--OUT)") (class "Default")
      (node (ref "R18") (pin "2") (pinfunction "2_2") (pintype "passive"))
      (node (ref "R19") (pin "1") (pinfunction "1_1") (pintype "passive"))
      (node (ref "U$2") (pin "5") (pinfunction "-OUT_5") (pintype "bidirectional"))
    )
    (net (code "137") (name "Net-(U$2-VOCM)") (class "Default")
      (node (ref "C31") (pin "2") (pinfunction "2_2") (pintype "passive"))
      (node (ref "R20") (pin "2") (pinfunction "2_2") (pintype "passive"))
      (node (ref "R21") (pin "1") (pinfunction "1_1") (pintype "passive"))
      (node (ref "U$2") (pin "2") (pinfunction "VOCM_2") (pintype "bidirectional"))
    )
    (net (code "138") (name "Net-(U$3-+IN)") (class "Default")
      (node (ref "R27") (pin "2") (pinfunction "2_2") (pintype "passive"))
      (node (ref "R28") (pin "1") (pinfunction "1_1") (pintype "passive"))
      (node (ref "U$3") (pin "8") (pinfunction "+IN_8") (pintype "bidirectional"))
    )
    (net (code "139") (name "Net-(U$3-+OUT)") (class "Default")
      (node (ref "R25") (pin "2") (pinfunction "2_2") (pintype "passive"))
      (node (ref "R26") (pin "1") (pinfunction "1_1") (pintype "passive"))
      (node (ref "U$3") (pin "4") (pinfunction "+OUT_4") (pintype "bidirectional"))
    )
    (net (code "140") (name "Net-(U$3--IN)") (class "Default")
      (node (ref "R24") (pin "1") (pinfunction "1_1") (pintype "passive"))
      (node (ref "R25") (pin "1") (pinfunction "1_1") (pintype "passive"))
      (node (ref "U$3") (pin "1") (pinfunction "-IN_1") (pintype "bidirectional"))
    )
    (net (code "141") (name "Net-(U$3--OUT)") (class "Default")
      (node (ref "R28") (pin "2") (pinfunction "2_2") (pintype "passive"))
      (node (ref "R29") (pin "1") (pinfunction "1_1") (pintype "passive"))
      (node (ref "U$3") (pin "5") (pinfunction "-OUT_5") (pintype "bidirectional"))
    )
    (net (code "142") (name "Net-(U$3-VOCM)") (class "Default")
      (node (ref "C41") (pin "2") (pinfunction "2_2") (pintype "passive"))
      (node (ref "R30") (pin "2") (pinfunction "2_2") (pintype "passive"))
      (node (ref "R31") (pin "1") (pinfunction "1_1") (pintype "passive"))
      (node (ref "U$3") (pin "2") (pinfunction "VOCM_2") (pintype "bidirectional"))
    )
    (net (code "143") (name "Net-(U1-OUT)") (class "Default")
      (node (ref "R44") (pin "1") (pinfunction "1_1") (pintype "passive"))
      (node (ref "U1") (pin "P$3") (pinfunction "OUT_P$3") (pintype "output"))
    )
    (net (code "144") (name "Net-(U6-RF_IN)") (class "Default")
      (node (ref "C49") (pin "1") (pinfunction "1_1") (pintype "passive"))
      (node (ref "R34") (pin "1") (pinfunction "1_1") (pintype "passive"))
      (node (ref "U6") (pin "11") (pinfunction "RF_IN_11") (pintype "bidirectional"))
    )
    (net (code "145") (name "Net-(U6-VCC_RF)") (class "Default")
      (node (ref "R36") (pin "1") (pinfunction "1_1") (pintype "passive"))
      (node (ref "U6") (pin "14") (pinfunction "VCC_RF_14") (pintype "bidirectional"))
    )
    (net (code "146") (name "Net-(U8-FB)") (class "Default")
      (node (ref "C57") (pin "1") (pinfunction "1_1") (pintype "passive"))
      (node (ref "R52") (pin "1") (pinfunction "1_1") (pintype "passive"))
      (node (ref "R53") (pin "2") (pinfunction "2_2") (pintype "passive"))
      (node (ref "U8") (pin "5") (pinfunction "FB_5") (pintype "bidirectional"))
    )
    (net (code "147") (name "Net-(U8-SW)") (class "Default")
      (node (ref "L3") (pin "1") (pinfunction "1_1") (pintype "passive"))
      (node (ref "U8") (pin "3") (pinfunction "SW_3") (pintype "bidirectional"))
    )
    (net (code "148") (name "unconnected-(IC3-IOB_57-Pad38)") (class "Default")
      (node (ref "IC3") (pin "38") (pinfunction "IOB_57_38") (pintype "bidirectional"))
    )
    (net (code "149") (name "unconnected-(IC3-IOB_81_GBIN5-Pad49)") (class "Default")
      (node (ref "IC3") (pin "49") (pinfunction "IOB_81_GBIN5_49") (pintype "bidirectional"))
    )
    (net (code "150") (name "unconnected-(IC3-IOB_82_GBIN4-Pad52)") (class "Default")
      (node (ref "IC3") (pin "52") (pinfunction "IOB_82_GBIN4_52") (pintype "bidirectional"))
    )
    (net (code "151") (name "unconnected-(IC3-IOB_91-Pad55)") (class "Default")
      (node (ref "IC3") (pin "55") (pinfunction "IOB_91_55") (pintype "bidirectional"))
    )
    (net (code "152") (name "unconnected-(IC3-IOB_94-Pad56)") (class "Default")
      (node (ref "IC3") (pin "56") (pinfunction "IOB_94_56") (pintype "bidirectional"))
    )
    (net (code "153") (name "unconnected-(IC3-IOB_95-Pad60)") (class "Default")
      (node (ref "IC3") (pin "60") (pinfunction "IOB_95_60") (pintype "bidirectional"))
    )
    (net (code "154") (name "unconnected-(IC3-IOB_102-Pad62)") (class "Default")
      (node (ref "IC3") (pin "62") (pinfunction "IOB_102_62") (pintype "bidirectional"))
    )
    (net (code "155") (name "unconnected-(IC3-IOL_3A-Pad3)") (class "Default")
      (node (ref "IC3") (pin "3") (pinfunction "IOL_3A_3") (pintype "bidirectional"))
    )
    (net (code "156") (name "unconnected-(IC3-IOL_3B-Pad4)") (class "Default")
      (node (ref "IC3") (pin "4") (pinfunction "IOL_3B_4") (pintype "bidirectional"))
    )
    (net (code "157") (name "unconnected-(IC3-IOL_4A-Pad7)") (class "Default")
      (node (ref "IC3") (pin "7") (pinfunction "IOL_4A_7") (pintype "bidirectional"))
    )
    (net (code "158") (name "unconnected-(IC3-IOL_4B-Pad8)") (class "Default")
      (node (ref "IC3") (pin "8") (pinfunction "IOL_4B_8") (pintype "bidirectional"))
    )
    (net (code "159") (name "unconnected-(IC3-IOL_5A-Pad9)") (class "Default")
      (node (ref "IC3") (pin "9") (pinfunction "IOL_5A_9") (pintype "bidirectional"))
    )
    (net (code "160") (name "unconnected-(IC3-IOL_5B-Pad10)") (class "Default")
      (node (ref "IC3") (pin "10") (pinfunction "IOL_5B_10") (pintype "bidirectional"))
    )
    (net (code "161") (name "unconnected-(IC3-IOL_18B-Pad26)") (class "Default")
      (node (ref "IC3") (pin "26") (pinfunction "IOL_18B_26") (pintype "bidirectional"))
    )
    (net (code "162") (name "unconnected-(IC3-IOL_23A-Pad28)") (class "Default")
      (node (ref "IC3") (pin "28") (pinfunction "IOL_23A_28") (pintype "bidirectional"))
    )
    (net (code "163") (name "unconnected-(IC3-IOL_23B-Pad29)") (class "Default")
      (node (ref "IC3") (pin "29") (pinfunction "IOL_23B_29") (pintype "bidirectional"))
    )
    (net (code "164") (name "unconnected-(IC3-IOL_24A-Pad31)") (class "Default")
      (node (ref "IC3") (pin "31") (pinfunction "IOL_24A_31") (pintype "bidirectional"))
    )
    (net (code "165") (name "unconnected-(IC3-IOL_24B-Pad32)") (class "Default")
      (node (ref "IC3") (pin "32") (pinfunction "IOL_24B_32") (pintype "bidirectional"))
    )
    (net (code "166") (name "unconnected-(IC3-IOL_25A-Pad33)") (class "Default")
      (node (ref "IC3") (pin "33") (pinfunction "IOL_25A_33") (pintype "bidirectional"))
    )
    (net (code "167") (name "unconnected-(IC3-IOL_25B-Pad34)") (class "Default")
      (node (ref "IC3") (pin "34") (pinfunction "IOL_25B_34") (pintype "bidirectional"))
    )
    (net (code "168") (name "unconnected-(IC3-IOR_109-Pad73)") (class "Default")
      (node (ref "IC3") (pin "73") (pinfunction "IOR_109_73") (pintype "bidirectional"))
    )
    (net (code "169") (name "unconnected-(IC3-IOR_110-Pad74)") (class "Default")
      (node (ref "IC3") (pin "74") (pinfunction "IOR_110_74") (pintype "bidirectional"))
    )
    (net (code "170") (name "unconnected-(IC3-IOR_111-Pad75)") (class "Default")
      (node (ref "IC3") (pin "75") (pinfunction "IOR_111_75") (pintype "bidirectional"))
    )
    (net (code "171") (name "unconnected-(IC3-IOR_112-Pad76)") (class "Default")
      (node (ref "IC3") (pin "76") (pinfunction "IOR_112_76") (pintype "bidirectional"))
    )
    (net (code "172") (name "unconnected-(IC3-IOR_114-Pad78)") (class "Default")
      (node (ref "IC3") (pin "78") (pinfunction "IOR_114_78") (pintype "bidirectional"))
    )
    (net (code "173") (name "unconnected-(IC3-IOR_115-Pad79)") (class "Default")
      (node (ref "IC3") (pin "79") (pinfunction "IOR_115_79") (pintype "bidirectional"))
    )
    (net (code "174") (name "unconnected-(IC3-IOR_116-Pad80)") (class "Default")
      (node (ref "IC3") (pin "80") (pinfunction "IOR_116_80") (pintype "bidirectional"))
    )
    (net (code "175") (name "unconnected-(IC3-IOR_117-Pad81)") (class "Default")
      (node (ref "IC3") (pin "81") (pinfunction "IOR_117_81") (pintype "bidirectional"))
    )
    (net (code "176") (name "unconnected-(IC3-IOR_118-Pad82)") (class "Default")
      (node (ref "IC3") (pin "82") (pinfunction "IOR_118_82") (pintype "bidirectional"))
    )
    (net (code "177") (name "unconnected-(IC3-IOR_120-Pad84)") (class "Default")
      (node (ref "IC3") (pin "84") (pinfunction "IOR_120_84") (pintype "bidirectional"))
    )
    (net (code "178") (name "unconnected-(IC3-IOR_128-Pad85)") (class "Default")
      (node (ref "IC3") (pin "85") (pinfunction "IOR_128_85") (pintype "bidirectional"))
    )
    (net (code "179") (name "unconnected-(IC3-IOR_136-Pad87)") (class "Default")
      (node (ref "IC3") (pin "87") (pinfunction "IOR_136_87") (pintype "bidirectional"))
    )
    (net (code "180") (name "unconnected-(IC3-IOR_137-Pad88)") (class "Default")
      (node (ref "IC3") (pin "88") (pinfunction "IOR_137_88") (pintype "bidirectional"))
    )
    (net (code "181") (name "unconnected-(IC3-IOR_138-Pad90)") (class "Default")
      (node (ref "IC3") (pin "90") (pinfunction "IOR_138_90") (pintype "bidirectional"))
    )
    (net (code "182") (name "unconnected-(IC3-IOR_139-Pad91)") (class "Default")
      (node (ref "IC3") (pin "91") (pinfunction "IOR_139_91") (pintype "bidirectional"))
    )
    (net (code "183") (name "unconnected-(IC3-IOR_141_GBIN2-Pad94)") (class "Default")
      (node (ref "IC3") (pin "94") (pinfunction "IOR_141_GBIN2_94") (pintype "bidirectional"))
    )
    (net (code "184") (name "unconnected-(IC3-IOT_190-Pad122)") (class "Default")
      (node (ref "IC3") (pin "122") (pinfunction "IOT_190_122") (pintype "bidirectional"))
    )
    (net (code "185") (name "unconnected-(IC3-IOT_191-Pad124)") (class "Default")
      (node (ref "IC3") (pin "124") (pinfunction "IOT_191_124") (pintype "bidirectional"))
    )
    (net (code "186") (name "unconnected-(IC3-IOT_192-Pad125)") (class "Default")
      (node (ref "IC3") (pin "125") (pinfunction "IOT_192_125") (pintype "bidirectional"))
    )
    (net (code "187") (name "unconnected-(IC3-IOT_197_GBIN1-Pad128)") (class "Default")
      (node (ref "IC3") (pin "128") (pinfunction "IOT_197_GBIN1_128") (pintype "bidirectional"))
    )
    (net (code "188") (name "unconnected-(IC3-IOT_206-Pad130)") (class "Default")
      (node (ref "IC3") (pin "130") (pinfunction "IOT_206_130") (pintype "bidirectional"))
    )
    (net (code "189") (name "unconnected-(IC3-NC-Pad35)") (class "Default")
      (node (ref "IC3") (pin "35") (pinfunction "NC_35") (pintype "bidirectional"))
    )
    (net (code "190") (name "unconnected-(IC3-NC-Pad36)") (class "Default")
      (node (ref "IC3") (pin "36") (pinfunction "NC_36") (pintype "bidirectional"))
    )
    (net (code "191") (name "unconnected-(IC3-NC-Pad50)") (class "Default")
      (node (ref "IC3") (pin "50") (pinfunction "NC_50") (pintype "bidirectional"))
    )
    (net (code "192") (name "unconnected-(IC3-NC-Pad51)") (class "Default")
      (node (ref "IC3") (pin "51") (pinfunction "NC_51") (pintype "bidirectional"))
    )
    (net (code "193") (name "unconnected-(IC3-NC-Pad58)") (class "Default")
      (node (ref "IC3") (pin "58") (pinfunction "NC_58") (pintype "bidirectional"))
    )
    (net (code "194") (name "unconnected-(IC3-NC-Pad77)") (class "Default")
      (node (ref "IC3") (pin "77") (pinfunction "NC_77") (pintype "bidirectional"))
    )
    (net (code "195") (name "unconnected-(IC3-NC-Pad133)") (class "Default")
      (node (ref "IC3") (pin "133") (pinfunction "NC_133") (pintype "bidirectional"))
    )
    (net (code "196") (name "unconnected-(IC3-VPP_FAST-Pad109)") (class "Default")
      (node (ref "IC3") (pin "109") (pinfunction "VPP_FAST_109") (pintype "bidirectional"))
    )
    (net (code "197") (name "unconnected-(J5-GND-Pad2)") (class "Default")
      (node (ref "J5") (pin "2") (pinfunction "GND_2") (pintype "passive"))
    )
    (net (code "198") (name "unconnected-(J5-GND-Pad3)") (class "Default")
      (node (ref "J5") (pin "3") (pinfunction "GND_3") (pintype "passive"))
    )
    (net (code "199") (name "unconnected-(J5-GND-Pad4)") (class "Default")
      (node (ref "J5") (pin "4") (pinfunction "GND_4") (pintype "passive"))
    )
    (net (code "200") (name "unconnected-(PI_GPIO-Pad17)") (class "Default")
      (node (ref "PI_GPIO") (pin "17") (pinfunction "17_17") (pintype "passive"))
    )
    (net (code "201") (name "unconnected-(U$1-DNC$1-Pad23)") (class "Default")
      (node (ref "U$1") (pin "23") (pinfunction "DNC$1_23") (pintype "bidirectional"))
    )
    (net (code "202") (name "unconnected-(U$1-DNC$2-Pad24)") (class "Default")
      (node (ref "U$1") (pin "24") (pinfunction "DNC$2_24") (pintype "bidirectional"))
    )
    (net (code "203") (name "unconnected-(U$1-DNC$3-Pad25)") (class "Default")
      (node (ref "U$1") (pin "25") (pinfunction "DNC$3_25") (pintype "bidirectional"))
    )
    (net (code "204") (name "unconnected-(U$1-DNC$4-Pad26)") (class "Default")
      (node (ref "U$1") (pin "26") (pinfunction "DNC$4_26") (pintype "bidirectional"))
    )
    (net (code "205") (name "unconnected-(U$1-DNC$5-Pad42)") (class "Default")
      (node (ref "U$1") (pin "42") (pinfunction "DNC$5_42") (pintype "bidirectional"))
    )
    (net (code "206") (name "unconnected-(U$1-DNC$6-Pad43)") (class "Default")
      (node (ref "U$1") (pin "43") (pinfunction "DNC$6_43") (pintype "bidirectional"))
    )
    (net (code "207") (name "unconnected-(U$1-DNC$7-Pad44)") (class "Default")
      (node (ref "U$1") (pin "44") (pinfunction "DNC$7_44") (pintype "bidirectional"))
    )
    (net (code "208") (name "unconnected-(U$1-DNC$8-Pad45)") (class "Default")
      (node (ref "U$1") (pin "45") (pinfunction "DNC$8_45") (pintype "bidirectional"))
    )
    (net (code "209") (name "unconnected-(U$1-DNC$9-Pad58)") (class "Default")
      (node (ref "U$1") (pin "58") (pinfunction "DNC$9_58") (pintype "bidirectional"))
    )
    (net (code "210") (name "unconnected-(U$1-DNC-Pad39)") (class "Default")
      (node (ref "U$1") (pin "39") (pinfunction "DNC_39") (pintype "bidirectional"))
    )
    (net (code "211") (name "unconnected-(U$2-NC-Pad7)") (class "Default")
      (node (ref "U$2") (pin "7") (pinfunction "NC_7") (pintype "bidirectional"))
    )
    (net (code "212") (name "unconnected-(U$3-NC-Pad7)") (class "Default")
      (node (ref "U$3") (pin "7") (pinfunction "NC_7") (pintype "bidirectional"))
    )
    (net (code "213") (name "unconnected-(U3-NC-Pad2)") (class "Default")
      (node (ref "U3") (pin "2") (pinfunction "NC_2") (pintype "bidirectional"))
    )
    (net (code "214") (name "unconnected-(U3-NC-Pad3)") (class "Default")
      (node (ref "U3") (pin "3") (pinfunction "NC_3") (pintype "bidirectional"))
    )
    (net (code "215") (name "unconnected-(U3-NC-Pad4)") (class "Default")
      (node (ref "U3") (pin "4") (pinfunction "NC_4") (pintype "bidirectional"))
    )
    (net (code "216") (name "unconnected-(U3-NC-Pad5)") (class "Default")
      (node (ref "U3") (pin "5") (pinfunction "NC_5") (pintype "bidirectional"))
    )
    (net (code "217") (name "unconnected-(U3-NC-Pad6)") (class "Default")
      (node (ref "U3") (pin "6") (pinfunction "NC_6") (pintype "bidirectional"))
    )
    (net (code "218") (name "unconnected-(U3-NC-Pad14)") (class "Default")
      (node (ref "U3") (pin "14") (pinfunction "NC_14") (pintype "bidirectional"))
    )
    (net (code "219") (name "unconnected-(U3-NC-Pad15)") (class "Default")
      (node (ref "U3") (pin "15") (pinfunction "NC_15") (pintype "bidirectional"))
    )
    (net (code "220") (name "unconnected-(U3-NC-Pad16)") (class "Default")
      (node (ref "U3") (pin "16") (pinfunction "NC_16") (pintype "bidirectional"))
    )
    (net (code "221") (name "unconnected-(U3-NC-Pad17)") (class "Default")
      (node (ref "U3") (pin "17") (pinfunction "NC_17") (pintype "bidirectional"))
    )
    (net (code "222") (name "unconnected-(U3-RESV-Pad19)") (class "Default")
      (node (ref "U3") (pin "19") (pinfunction "RESV_19") (pintype "bidirectional"))
    )
    (net (code "223") (name "unconnected-(U6-ANTON-Pad13)") (class "Default")
      (node (ref "U6") (pin "13") (pinfunction "ANTON_13") (pintype "bidirectional"))
    )
    (net (code "224") (name "unconnected-(U6-NC-Pad7)") (class "Default")
      (node (ref "U6") (pin "7") (pinfunction "NC_7") (pintype "bidirectional"))
    )
    (net (code "225") (name "unconnected-(U6-NC-Pad15)") (class "Default")
      (node (ref "U6") (pin "15") (pinfunction "NC_15") (pintype "bidirectional"))
    )
    (net (code "226") (name "unconnected-(U6-RESERVED-Pad16)") (class "Default")
      (node (ref "U6") (pin "16") (pinfunction "RESERVED_16") (pintype "bidirectional"))
    )
    (net (code "227") (name "unconnected-(U6-RESERVED-Pad17)") (class "Default")
      (node (ref "U6") (pin "17") (pinfunction "RESERVED_17") (pintype "bidirectional"))
    )
    (net (code "228") (name "unconnected-(U6-STANDBY-Pad5)") (class "Default")
      (node (ref "U6") (pin "5") (pinfunction "STANDBY_5") (pintype "bidirectional"))
    )
    (net (code "229") (name "unconnected-(U6-V_BCKP-Pad6)") (class "Default")
      (node (ref "U6") (pin "6") (pinfunction "V_BCKP_6") (pintype "bidirectional"))
    )
    (net (code "230") (name "unconnected-(U7-NC-Pad3)") (class "Default")
      (node (ref "U7") (pin "3") (pinfunction "NC_3") (pintype "no_connect"))
    )
    (net (code "231") (name "unconnected-(USB1-DM-Pad2)") (class "Default")
      (node (ref "USB1") (pin "2") (pinfunction "DM_2") (pintype "bidirectional"))
    )
    (net (code "232") (name "unconnected-(USB1-DP-Pad3)") (class "Default")
      (node (ref "USB1") (pin "3") (pinfunction "DP_3") (pintype "bidirectional"))
    )
    (net (code "233") (name "unconnected-(USB1-ID-Pad4)") (class "Default")
      (node (ref "USB1") (pin "4") (pinfunction "ID_4") (pintype "bidirectional"))
    )
  )
)
